# RX08b.net
KiCad netlist of a schematic drawn in EAGLE
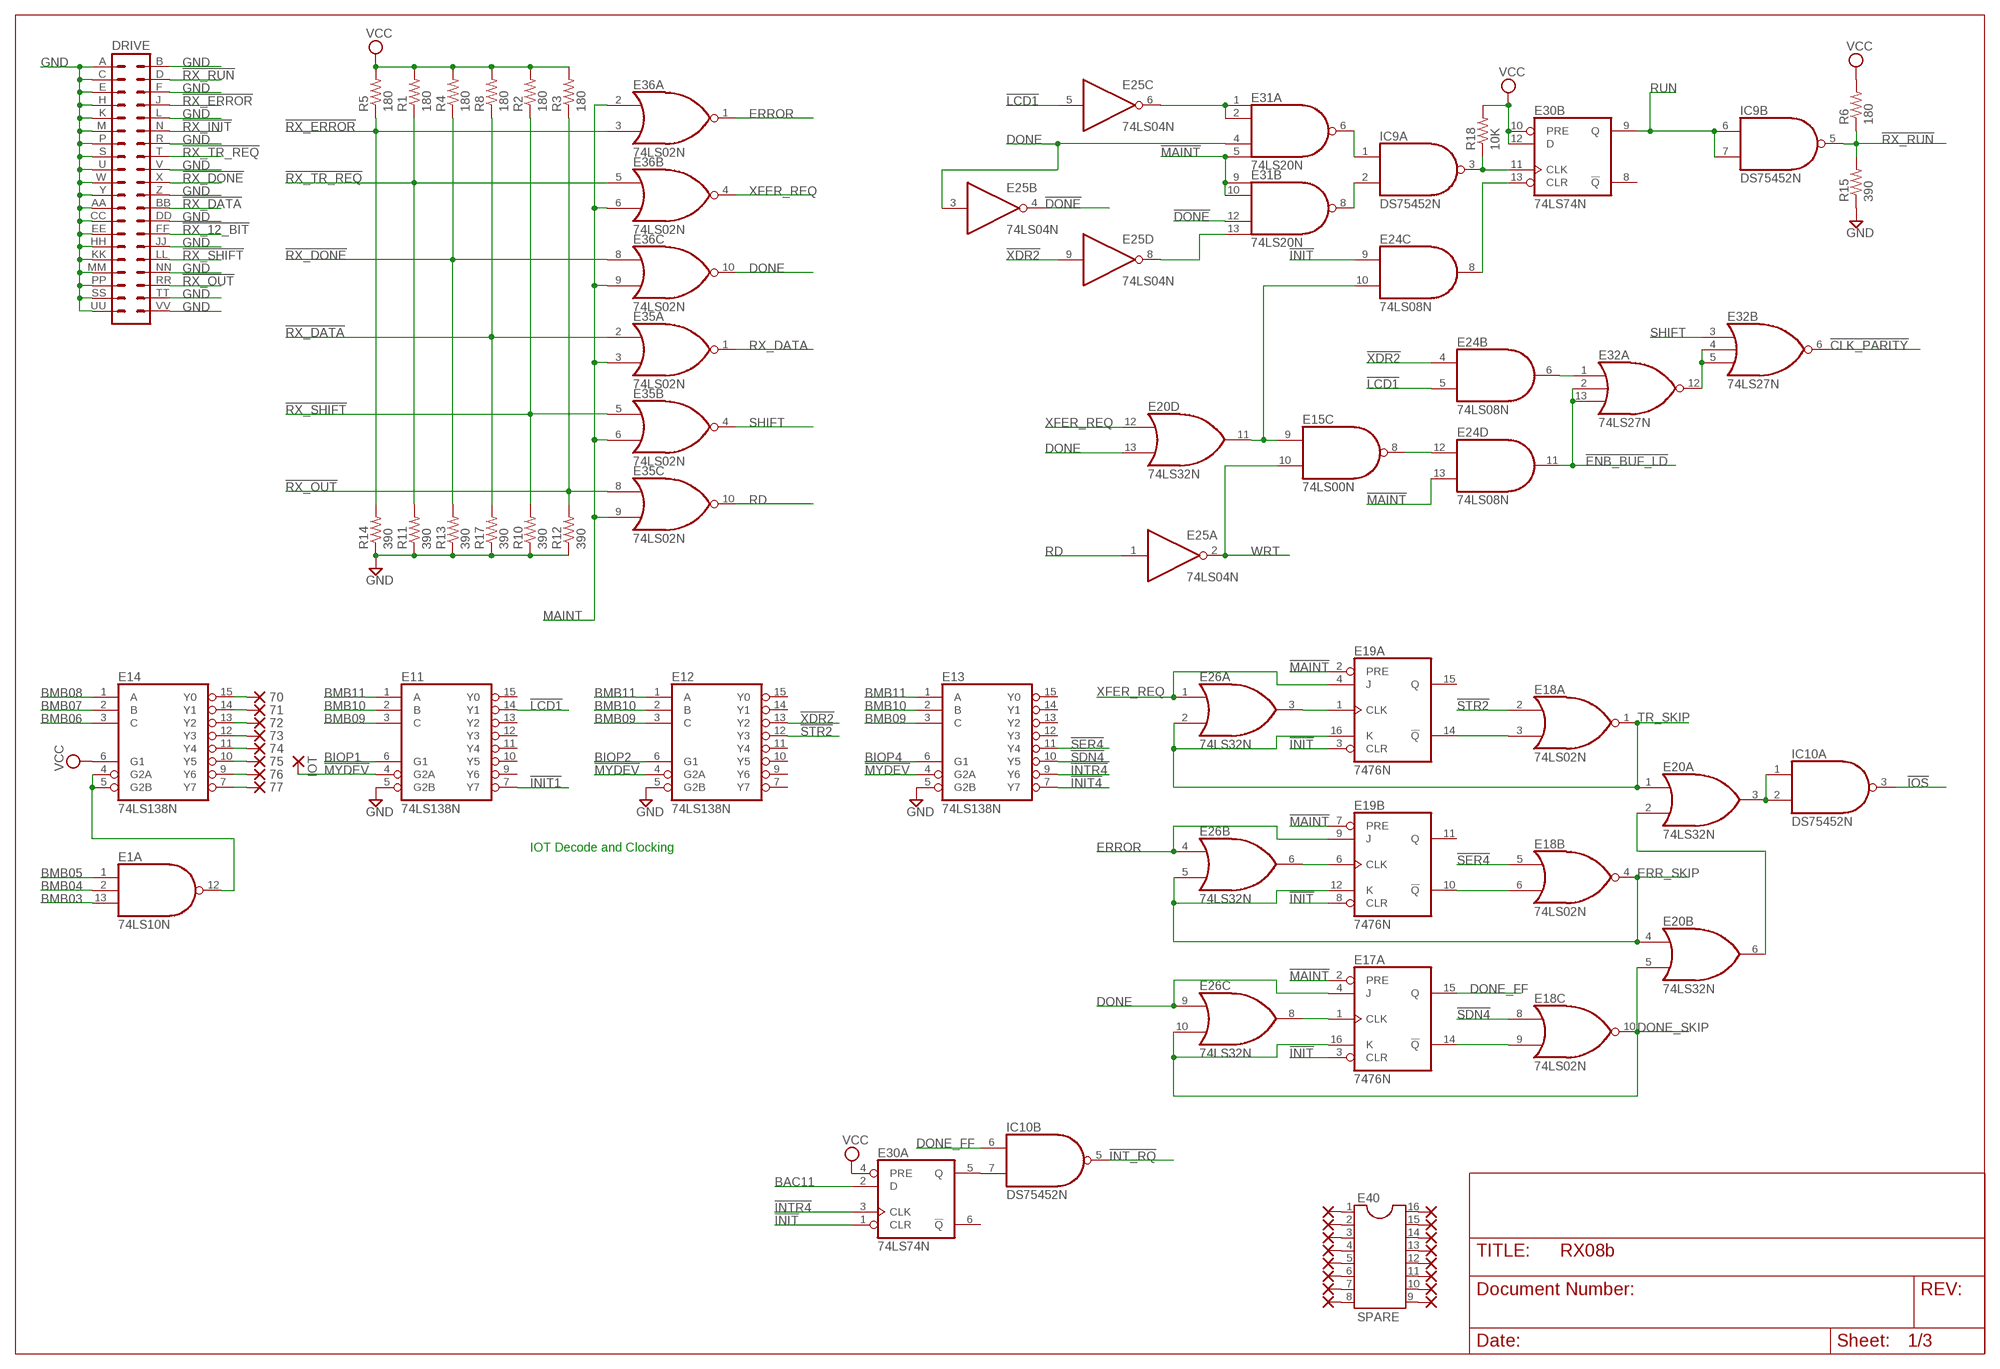
[diagram p0: schematic, sheet 1]
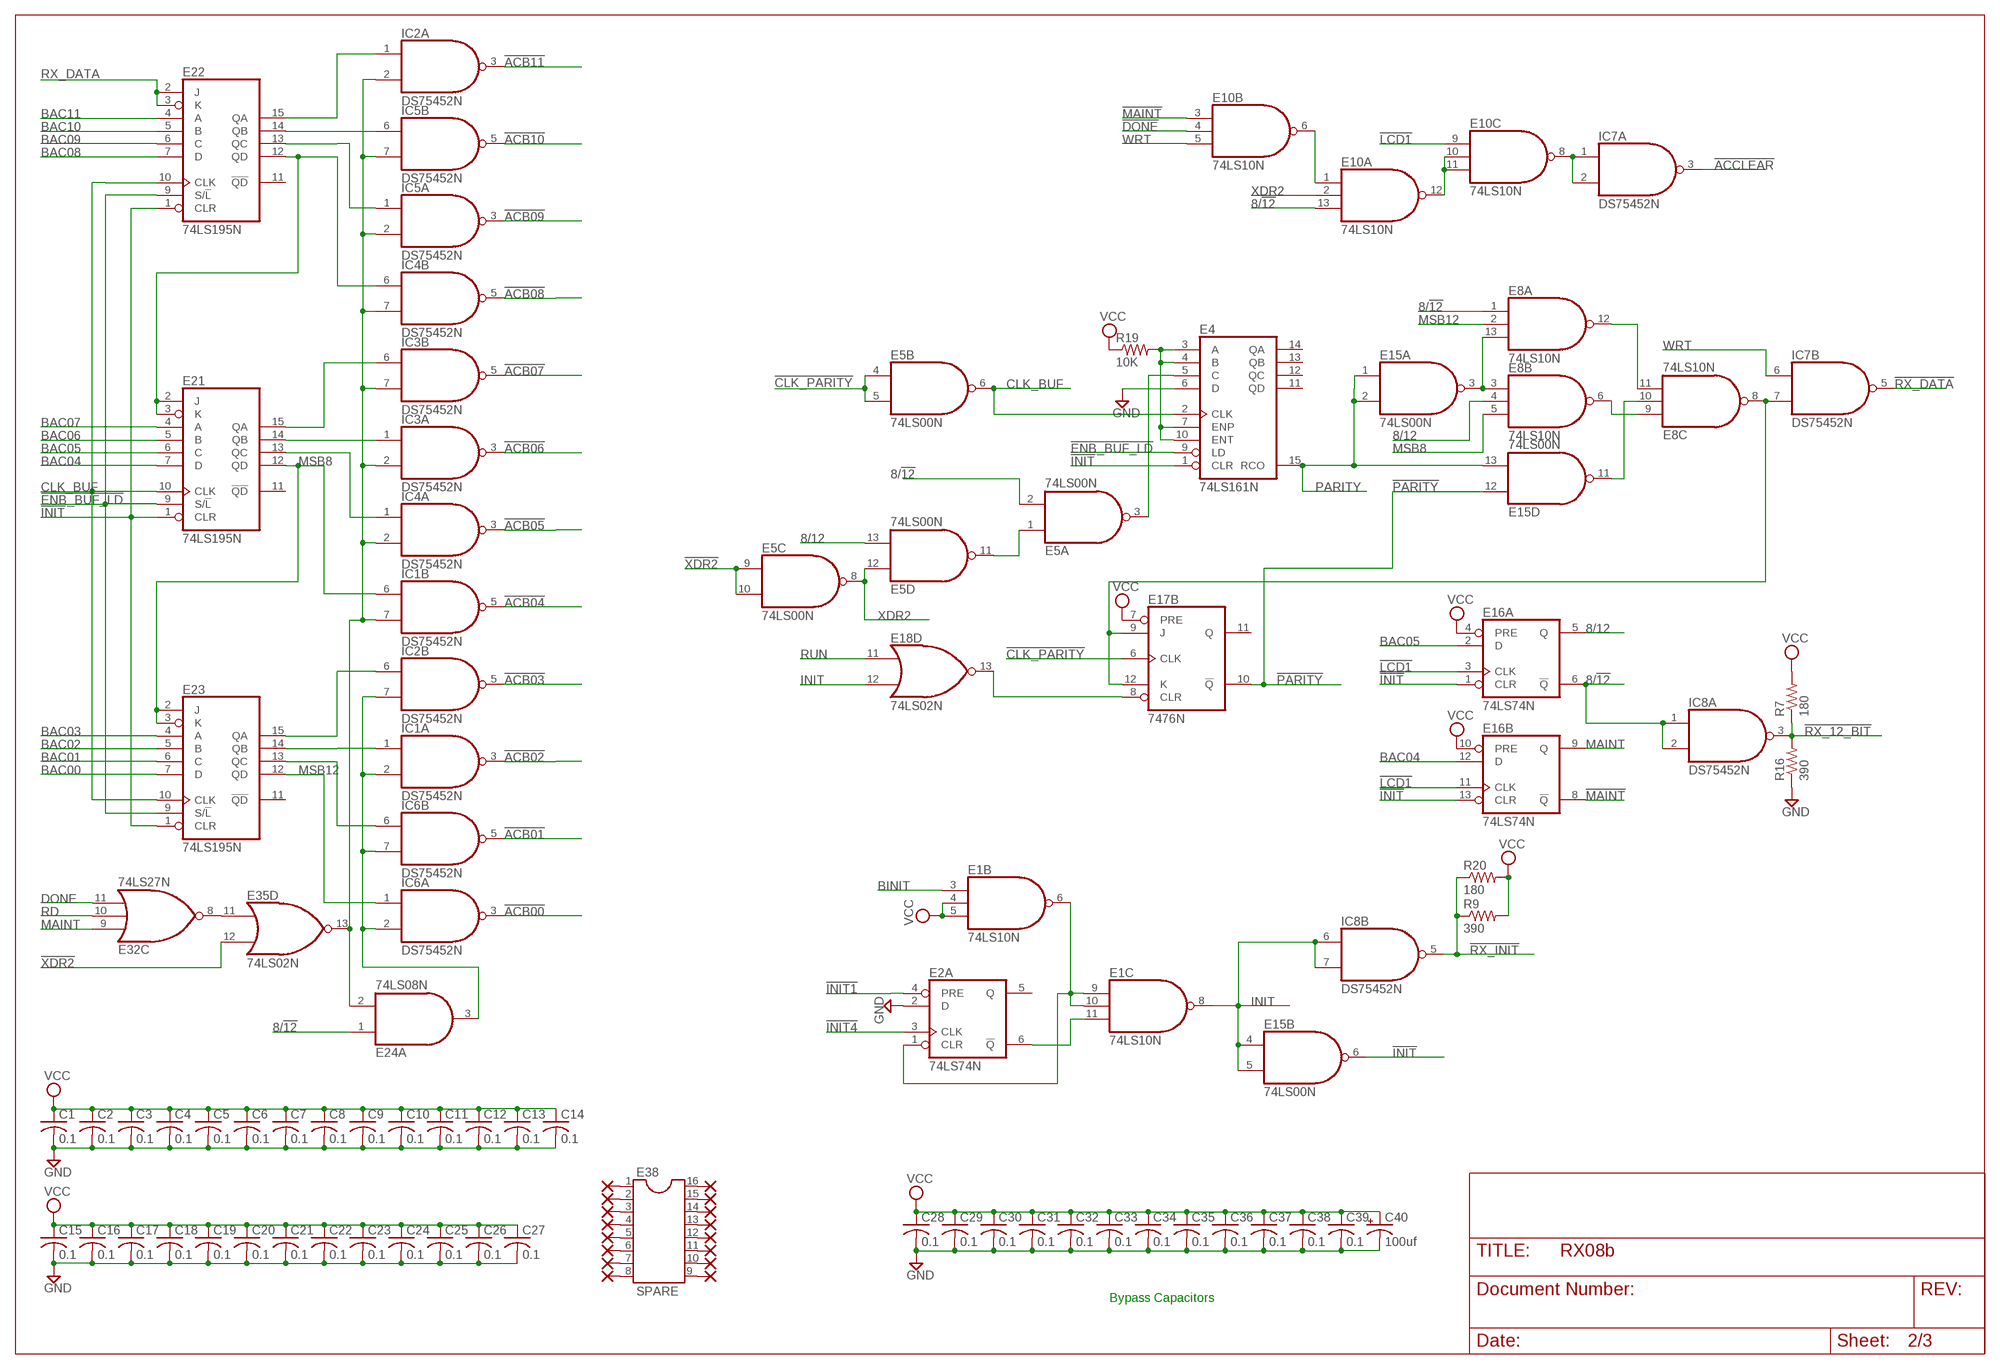
[diagram p1: schematic, sheet 2]
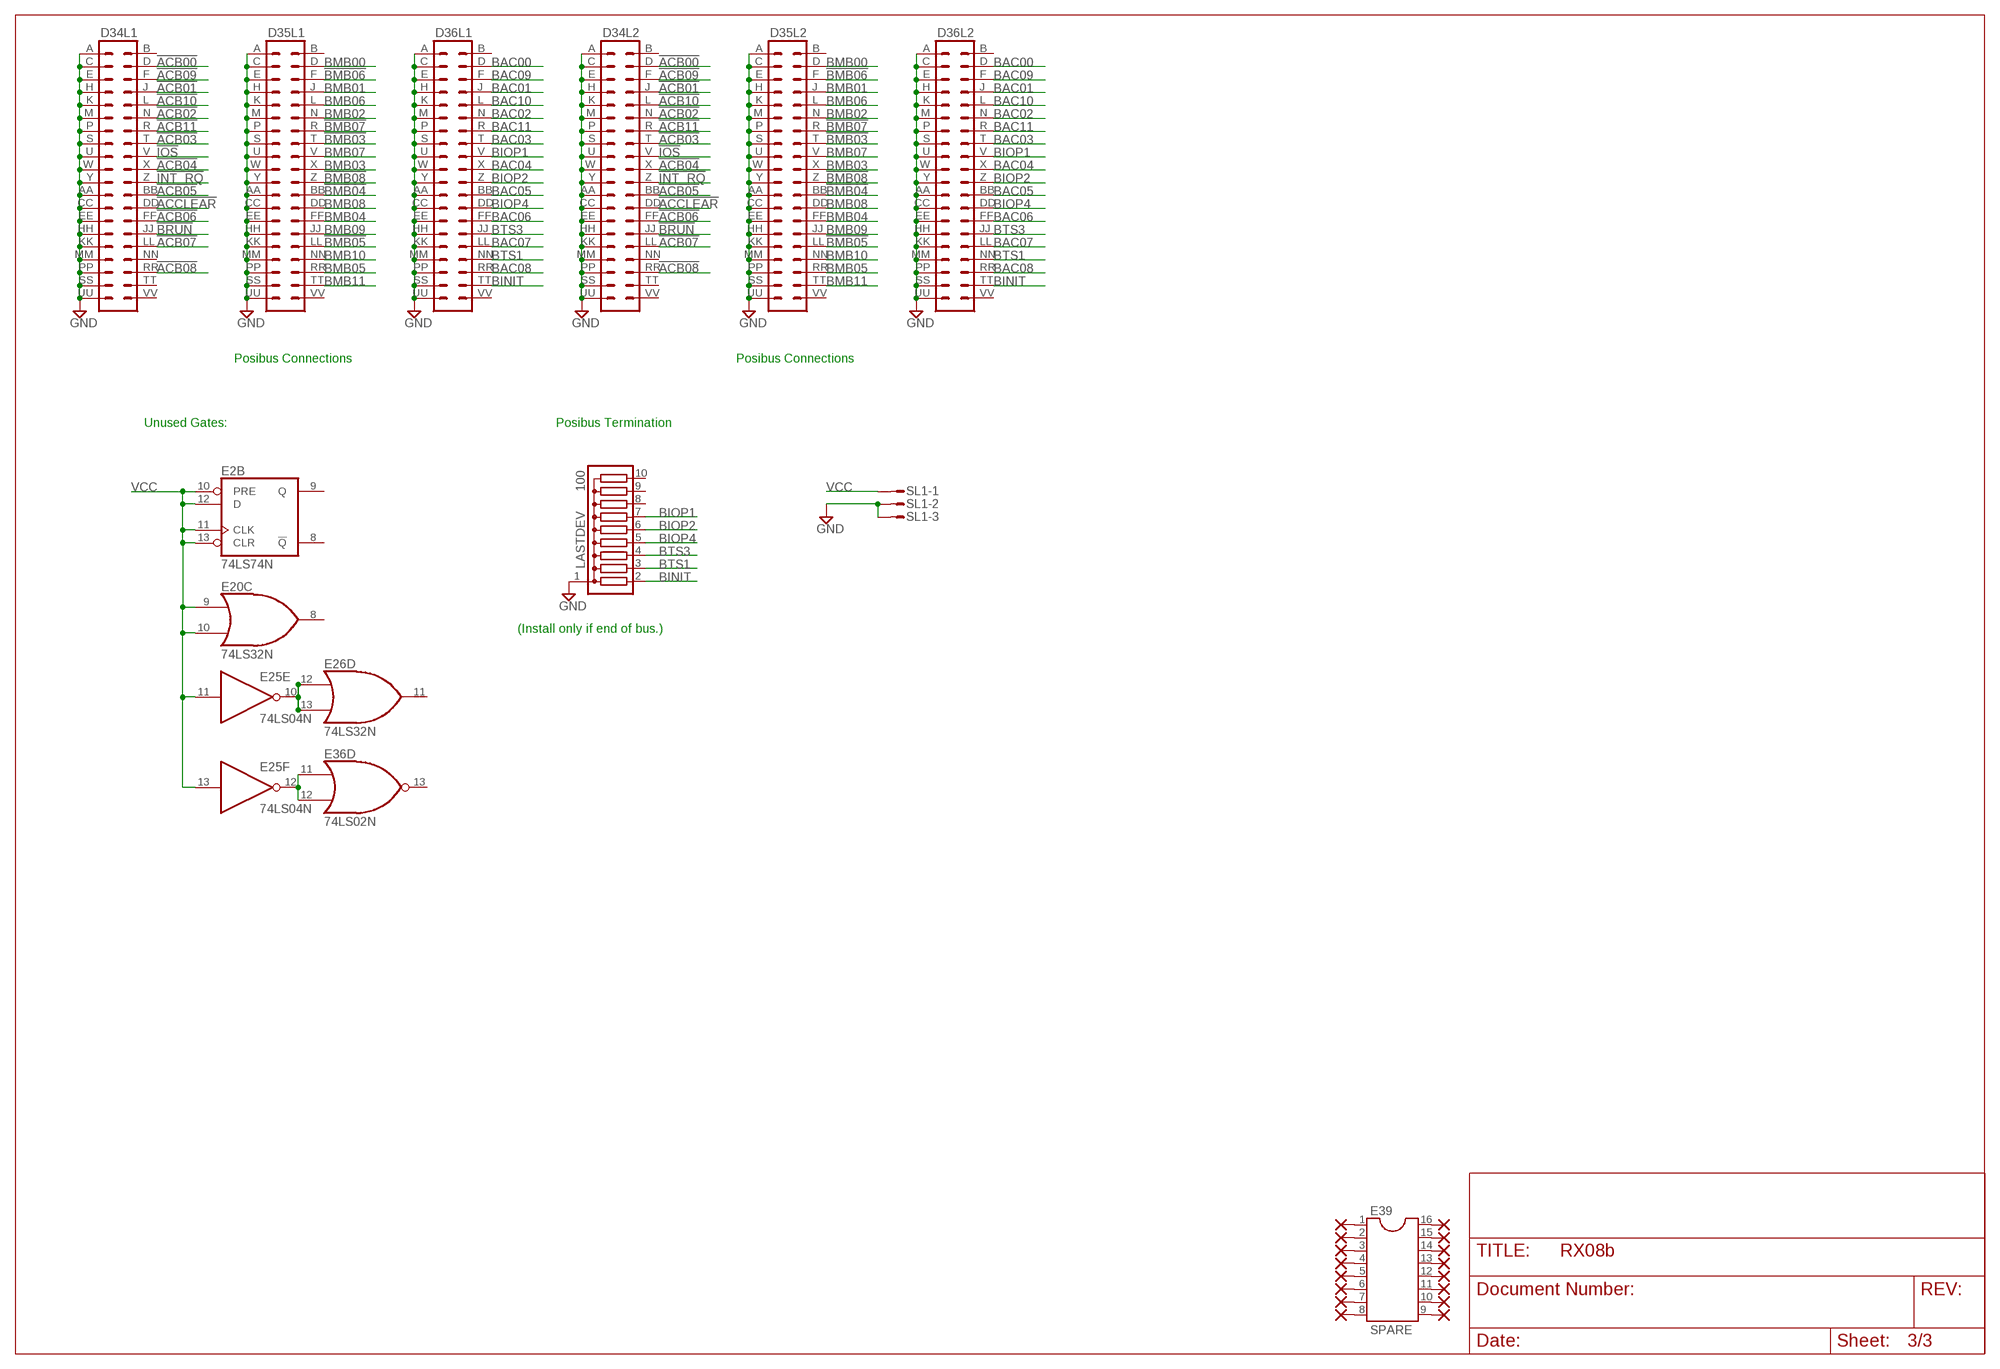
[diagram p2: schematic, sheet 3]

(export (version "E")
  (design (tool "Eeschema 10.0.6"))
  (components
    (comp (ref "C1")
      (value "0.1")
      (footprint "eagle-import:C050-025X075")
      (libsource (lib "eagle-import") (part "C-US050-025X075"))
    )
    (comp (ref "C2")
      (value "0.1")
      (footprint "eagle-import:C050-025X075")
      (libsource (lib "eagle-import") (part "C-US050-025X075"))
    )
    (comp (ref "C3")
      (value "0.1")
      (footprint "eagle-import:C050-025X075")
      (libsource (lib "eagle-import") (part "C-US050-025X075"))
    )
    (comp (ref "C4")
      (value "0.1")
      (footprint "eagle-import:C050-025X075")
      (libsource (lib "eagle-import") (part "C-US050-025X075"))
    )
    (comp (ref "C5")
      (value "0.1")
      (footprint "eagle-import:C050-025X075")
      (libsource (lib "eagle-import") (part "C-US050-025X075"))
    )
    (comp (ref "C6")
      (value "0.1")
      (footprint "eagle-import:C050-025X075")
      (libsource (lib "eagle-import") (part "C-US050-025X075"))
    )
    (comp (ref "C7")
      (value "0.1")
      (footprint "eagle-import:C050-025X075")
      (libsource (lib "eagle-import") (part "C-US050-025X075"))
    )
    (comp (ref "C8")
      (value "0.1")
      (footprint "eagle-import:C050-025X075")
      (libsource (lib "eagle-import") (part "C-US050-025X075"))
    )
    (comp (ref "C9")
      (value "0.1")
      (footprint "eagle-import:C050-025X075")
      (libsource (lib "eagle-import") (part "C-US050-025X075"))
    )
    (comp (ref "C10")
      (value "0.1")
      (footprint "eagle-import:C050-025X075")
      (libsource (lib "eagle-import") (part "C-US050-025X075"))
    )
    (comp (ref "C11")
      (value "0.1")
      (footprint "eagle-import:C050-025X075")
      (libsource (lib "eagle-import") (part "C-US050-025X075"))
    )
    (comp (ref "C12")
      (value "0.1")
      (footprint "eagle-import:C050-025X075")
      (libsource (lib "eagle-import") (part "C-US050-025X075"))
    )
    (comp (ref "C13")
      (value "0.1")
      (footprint "eagle-import:C050-025X075")
      (libsource (lib "eagle-import") (part "C-US050-025X075"))
    )
    (comp (ref "C14")
      (value "0.1")
      (footprint "eagle-import:C050-025X075")
      (libsource (lib "eagle-import") (part "C-US050-025X075"))
    )
    (comp (ref "C15")
      (value "0.1")
      (footprint "eagle-import:C050-025X075")
      (libsource (lib "eagle-import") (part "C-US050-025X075"))
    )
    (comp (ref "C16")
      (value "0.1")
      (footprint "eagle-import:C050-025X075")
      (libsource (lib "eagle-import") (part "C-US050-025X075"))
    )
    (comp (ref "C17")
      (value "0.1")
      (footprint "eagle-import:C050-025X075")
      (libsource (lib "eagle-import") (part "C-US050-025X075"))
    )
    (comp (ref "C18")
      (value "0.1")
      (footprint "eagle-import:C050-025X075")
      (libsource (lib "eagle-import") (part "C-US050-025X075"))
    )
    (comp (ref "C19")
      (value "0.1")
      (footprint "eagle-import:C050-025X075")
      (libsource (lib "eagle-import") (part "C-US050-025X075"))
    )
    (comp (ref "C20")
      (value "0.1")
      (footprint "eagle-import:C050-025X075")
      (libsource (lib "eagle-import") (part "C-US050-025X075"))
    )
    (comp (ref "C21")
      (value "0.1")
      (footprint "eagle-import:C050-025X075")
      (libsource (lib "eagle-import") (part "C-US050-025X075"))
    )
    (comp (ref "C22")
      (value "0.1")
      (footprint "eagle-import:C050-025X075")
      (libsource (lib "eagle-import") (part "C-US050-025X075"))
    )
    (comp (ref "C23")
      (value "0.1")
      (footprint "eagle-import:C050-025X075")
      (libsource (lib "eagle-import") (part "C-US050-025X075"))
    )
    (comp (ref "C24")
      (value "0.1")
      (footprint "eagle-import:C050-025X075")
      (libsource (lib "eagle-import") (part "C-US050-025X075"))
    )
    (comp (ref "C25")
      (value "0.1")
      (footprint "eagle-import:C050-025X075")
      (libsource (lib "eagle-import") (part "C-US050-025X075"))
    )
    (comp (ref "C26")
      (value "0.1")
      (footprint "eagle-import:C050-025X075")
      (libsource (lib "eagle-import") (part "C-US050-025X075"))
    )
    (comp (ref "C27")
      (value "0.1")
      (footprint "eagle-import:C050-025X075")
      (libsource (lib "eagle-import") (part "C-US050-025X075"))
    )
    (comp (ref "C28")
      (value "0.1")
      (footprint "eagle-import:C050-025X075")
      (libsource (lib "eagle-import") (part "C-US050-025X075"))
    )
    (comp (ref "C29")
      (value "0.1")
      (footprint "eagle-import:C050-025X075")
      (libsource (lib "eagle-import") (part "C-US050-025X075"))
    )
    (comp (ref "C30")
      (value "0.1")
      (footprint "eagle-import:C050-025X075")
      (libsource (lib "eagle-import") (part "C-US050-025X075"))
    )
    (comp (ref "C31")
      (value "0.1")
      (footprint "eagle-import:C050-025X075")
      (libsource (lib "eagle-import") (part "C-US050-025X075"))
    )
    (comp (ref "C32")
      (value "0.1")
      (footprint "eagle-import:C050-025X075")
      (libsource (lib "eagle-import") (part "C-US050-025X075"))
    )
    (comp (ref "C33")
      (value "0.1")
      (footprint "eagle-import:C050-025X075")
      (libsource (lib "eagle-import") (part "C-US050-025X075"))
    )
    (comp (ref "C34")
      (value "0.1")
      (footprint "eagle-import:C050-025X075")
      (libsource (lib "eagle-import") (part "C-US050-025X075"))
    )
    (comp (ref "C35")
      (value "0.1")
      (footprint "eagle-import:C050-025X075")
      (libsource (lib "eagle-import") (part "C-US050-025X075"))
    )
    (comp (ref "C36")
      (value "0.1")
      (footprint "eagle-import:C050-025X075")
      (libsource (lib "eagle-import") (part "C-US050-025X075"))
    )
    (comp (ref "C37")
      (value "0.1")
      (footprint "eagle-import:C050-025X075")
      (libsource (lib "eagle-import") (part "C-US050-025X075"))
    )
    (comp (ref "C38")
      (value "0.1")
      (footprint "eagle-import:C050-025X075")
      (libsource (lib "eagle-import") (part "C-US050-025X075"))
    )
    (comp (ref "C39")
      (value "0.1")
      (footprint "eagle-import:C050-025X075")
      (libsource (lib "eagle-import") (part "C-US050-025X075"))
    )
    (comp (ref "C40")
      (value "100uf")
      (footprint "eagle-import:E22-9")
      (libsource (lib "eagle-import") (part "CPOL-USE22-9AXIAL"))
    )
    (comp (ref "E1")
      (value "74LS10N")
      (footprint "eagle-import:DIL14")
      (libsource (lib "eagle-import") (part "7410NLS"))
    )
    (comp (ref "E2")
      (value "74LS74N")
      (footprint "eagle-import:DIL14")
      (libsource (lib "eagle-import") (part "7474NLS"))
    )
    (comp (ref "E4")
      (value "74LS161N")
      (footprint "eagle-import:DIL16")
      (libsource (lib "eagle-import") (part "74161NLS"))
    )
    (comp (ref "E5")
      (value "74LS00N")
      (footprint "eagle-import:DIL14")
      (libsource (lib "eagle-import") (part "7400NLS"))
    )
    (comp (ref "E8")
      (value "74LS10N")
      (footprint "eagle-import:DIL14")
      (libsource (lib "eagle-import") (part "7410NLS"))
    )
    (comp (ref "E10")
      (value "74LS10N")
      (footprint "eagle-import:DIL14")
      (libsource (lib "eagle-import") (part "7410NLS"))
    )
    (comp (ref "E15")
      (value "74LS00N")
      (footprint "eagle-import:DIL14")
      (libsource (lib "eagle-import") (part "7400NLS"))
    )
    (comp (ref "E16")
      (value "74LS74N")
      (footprint "eagle-import:DIL14")
      (libsource (lib "eagle-import") (part "7474NLS"))
    )
    (comp (ref "E17")
      (value "7476N")
      (footprint "eagle-import:DIL16")
      (libsource (lib "eagle-import") (part "7476N"))
    )
    (comp (ref "E18")
      (value "74LS02N")
      (footprint "eagle-import:DIL14")
      (libsource (lib "eagle-import") (part "7402NLS"))
    )
    (comp (ref "E21")
      (value "74LS195N")
      (footprint "eagle-import:DIL16")
      (libsource (lib "eagle-import") (part "74195NLS"))
    )
    (comp (ref "E22")
      (value "74LS195N")
      (footprint "eagle-import:DIL16")
      (libsource (lib "eagle-import") (part "74195NLS"))
    )
    (comp (ref "E23")
      (value "74LS195N")
      (footprint "eagle-import:DIL16")
      (libsource (lib "eagle-import") (part "74195NLS"))
    )
    (comp (ref "E24")
      (value "74LS08N")
      (footprint "eagle-import:DIL14")
      (libsource (lib "eagle-import") (part "7408NLS"))
    )
    (comp (ref "E32")
      (value "74LS27N")
      (footprint "eagle-import:DIL14")
      (libsource (lib "eagle-import") (part "7427NLS"))
    )
    (comp (ref "E35")
      (value "74LS02N")
      (footprint "eagle-import:DIL14")
      (libsource (lib "eagle-import") (part "7402NLS"))
    )
    (comp (ref "E38")
      (value "SPARE")
      (footprint "eagle-import:DIL16")
      (libsource (lib "eagle-import") (part "DIL16"))
    )
    (comp (ref "IC1")
      (value "DS75452N")
      (footprint "eagle-import:DIL08")
      (libsource (lib "eagle-import") (part "DS75452N"))
    )
    (comp (ref "IC2")
      (value "DS75452N")
      (footprint "eagle-import:DIL08")
      (libsource (lib "eagle-import") (part "DS75452N"))
    )
    (comp (ref "IC3")
      (value "DS75452N")
      (footprint "eagle-import:DIL08")
      (libsource (lib "eagle-import") (part "DS75452N"))
    )
    (comp (ref "IC4")
      (value "DS75452N")
      (footprint "eagle-import:DIL08")
      (libsource (lib "eagle-import") (part "DS75452N"))
    )
    (comp (ref "IC5")
      (value "DS75452N")
      (footprint "eagle-import:DIL08")
      (libsource (lib "eagle-import") (part "DS75452N"))
    )
    (comp (ref "IC6")
      (value "DS75452N")
      (footprint "eagle-import:DIL08")
      (libsource (lib "eagle-import") (part "DS75452N"))
    )
    (comp (ref "IC7")
      (value "DS75452N")
      (footprint "eagle-import:DIL08")
      (libsource (lib "eagle-import") (part "DS75452N"))
    )
    (comp (ref "IC8")
      (value "DS75452N")
      (footprint "eagle-import:DIL08")
      (libsource (lib "eagle-import") (part "DS75452N"))
    )
    (comp (ref "PAD10")
      (value "1,6/0,8")
      (footprint "eagle-import:1,6_0,8")
      (libsource (lib "eagle-import") (part "1,6/0,8"))
    )
    (comp (ref "PAD11")
      (value "1,6/0,8")
      (footprint "eagle-import:1,6_0,8")
      (libsource (lib "eagle-import") (part "1,6/0,8"))
    )
    (comp (ref "PAD12")
      (value "1,6/0,8")
      (footprint "eagle-import:1,6_0,8")
      (libsource (lib "eagle-import") (part "1,6/0,8"))
    )
    (comp (ref "PAD13")
      (value "1,6/0,8")
      (footprint "eagle-import:1,6_0,8")
      (libsource (lib "eagle-import") (part "1,6/0,8"))
    )
    (comp (ref "PAD14")
      (value "1,6/0,8")
      (footprint "eagle-import:1,6_0,8")
      (libsource (lib "eagle-import") (part "1,6/0,8"))
    )
    (comp (ref "PAD15")
      (value "1,6/0,8")
      (footprint "eagle-import:1,6_0,8")
      (libsource (lib "eagle-import") (part "1,6/0,8"))
    )
    (comp (ref "PAD16")
      (value "1,6/0,8")
      (footprint "eagle-import:1,6_0,8")
      (libsource (lib "eagle-import") (part "1,6/0,8"))
    )
    (comp (ref "PAD17")
      (value "1,6/0,8")
      (footprint "eagle-import:1,6_0,8")
      (libsource (lib "eagle-import") (part "1,6/0,8"))
    )
    (comp (ref "PAD20")
      (value "1,6/0,8")
      (footprint "eagle-import:1,6_0,8")
      (libsource (lib "eagle-import") (part "1,6/0,8"))
    )
    (comp (ref "PAD21")
      (value "1,6/0,8")
      (footprint "eagle-import:1,6_0,8")
      (libsource (lib "eagle-import") (part "1,6/0,8"))
    )
    (comp (ref "PAD22")
      (value "1,6/0,8")
      (footprint "eagle-import:1,6_0,8")
      (libsource (lib "eagle-import") (part "1,6/0,8"))
    )
    (comp (ref "PAD23")
      (value "1,6/0,8")
      (footprint "eagle-import:1,6_0,8")
      (libsource (lib "eagle-import") (part "1,6/0,8"))
    )
    (comp (ref "PAD24")
      (value "1,6/0,8")
      (footprint "eagle-import:1,6_0,8")
      (libsource (lib "eagle-import") (part "1,6/0,8"))
    )
    (comp (ref "PAD25")
      (value "1,6/0,8")
      (footprint "eagle-import:1,6_0,8")
      (libsource (lib "eagle-import") (part "1,6/0,8"))
    )
    (comp (ref "PAD26")
      (value "1,6/0,8")
      (footprint "eagle-import:1,6_0,8")
      (libsource (lib "eagle-import") (part "1,6/0,8"))
    )
    (comp (ref "PAD27")
      (value "1,6/0,8")
      (footprint "eagle-import:1,6_0,8")
      (libsource (lib "eagle-import") (part "1,6/0,8"))
    )
    (comp (ref "R7")
      (value "180")
      (footprint "eagle-import:0207_10")
      (libsource (lib "eagle-import") (part "R-US_0207/10"))
    )
    (comp (ref "R9")
      (value "390")
      (footprint "eagle-import:0207_10")
      (libsource (lib "eagle-import") (part "R-US_0207/10"))
    )
    (comp (ref "R16")
      (value "390")
      (footprint "eagle-import:0207_10")
      (libsource (lib "eagle-import") (part "R-US_0207/10"))
    )
    (comp (ref "R19")
      (value "10K")
      (footprint "eagle-import:0207_10")
      (libsource (lib "eagle-import") (part "R-US_0207/10"))
    )
    (comp (ref "R20")
      (value "180")
      (footprint "eagle-import:0207_10")
      (libsource (lib "eagle-import") (part "R-US_0207/10"))
    )
    (comp (ref "70")
      (value "1,6/0,8")
      (footprint "eagle-import:1,6_0,8")
      (libsource (lib "eagle-import") (part "1,6/0,8"))
    )
    (comp (ref "71")
      (value "1,6/0,8")
      (footprint "eagle-import:1,6_0,8")
      (libsource (lib "eagle-import") (part "1,6/0,8"))
    )
    (comp (ref "72")
      (value "1,6/0,8")
      (footprint "eagle-import:1,6_0,8")
      (libsource (lib "eagle-import") (part "1,6/0,8"))
    )
    (comp (ref "73")
      (value "1,6/0,8")
      (footprint "eagle-import:1,6_0,8")
      (libsource (lib "eagle-import") (part "1,6/0,8"))
    )
    (comp (ref "74")
      (value "1,6/0,8")
      (footprint "eagle-import:1,6_0,8")
      (libsource (lib "eagle-import") (part "1,6/0,8"))
    )
    (comp (ref "75")
      (value "1,6/0,8")
      (footprint "eagle-import:1,6_0,8")
      (libsource (lib "eagle-import") (part "1,6/0,8"))
    )
    (comp (ref "76")
      (value "1,6/0,8")
      (footprint "eagle-import:1,6_0,8")
      (libsource (lib "eagle-import") (part "1,6/0,8"))
    )
    (comp (ref "77")
      (value "1,6/0,8")
      (footprint "eagle-import:1,6_0,8")
      (libsource (lib "eagle-import") (part "1,6/0,8"))
    )
    (comp (ref "DRIVE")
      (value "DEC40PINV")
      (footprint "eagle-import:DEC40PINV")
      (libsource (lib "eagle-import") (part "DEC40PINV"))
    )
    (comp (ref "E11")
      (value "74LS138N")
      (footprint "eagle-import:DIL16")
      (libsource (lib "eagle-import") (part "74138NLS"))
    )
    (comp (ref "E12")
      (value "74LS138N")
      (footprint "eagle-import:DIL16")
      (libsource (lib "eagle-import") (part "74138NLS"))
    )
    (comp (ref "E13")
      (value "74LS138N")
      (footprint "eagle-import:DIL16")
      (libsource (lib "eagle-import") (part "74138NLS"))
    )
    (comp (ref "E14")
      (value "74LS138N")
      (footprint "eagle-import:DIL16")
      (libsource (lib "eagle-import") (part "74138NLS"))
    )
    (comp (ref "E19")
      (value "7476N")
      (footprint "eagle-import:DIL16")
      (libsource (lib "eagle-import") (part "7476N"))
    )
    (comp (ref "E20")
      (value "74LS32N")
      (footprint "eagle-import:DIL14")
      (libsource (lib "eagle-import") (part "7432NLS"))
    )
    (comp (ref "E25")
      (value "74LS04N")
      (footprint "eagle-import:DIL14")
      (libsource (lib "eagle-import") (part "7404NLS"))
    )
    (comp (ref "E26")
      (value "74LS32N")
      (footprint "eagle-import:DIL14")
      (libsource (lib "eagle-import") (part "7432NLS"))
    )
    (comp (ref "E30")
      (value "74LS74N")
      (footprint "eagle-import:DIL14")
      (libsource (lib "eagle-import") (part "7474NLS"))
    )
    (comp (ref "E31")
      (value "74LS20N")
      (footprint "eagle-import:DIL14")
      (libsource (lib "eagle-import") (part "7420NLS"))
    )
    (comp (ref "E36")
      (value "74LS02N")
      (footprint "eagle-import:DIL14")
      (libsource (lib "eagle-import") (part "7402NLS"))
    )
    (comp (ref "E40")
      (value "SPARE")
      (footprint "eagle-import:DIL16")
      (libsource (lib "eagle-import") (part "DIL16"))
    )
    (comp (ref "IC9")
      (value "DS75452N")
      (footprint "eagle-import:DIL08")
      (libsource (lib "eagle-import") (part "DS75452N"))
    )
    (comp (ref "IC10")
      (value "DS75452N")
      (footprint "eagle-import:DIL08")
      (libsource (lib "eagle-import") (part "DS75452N"))
    )
    (comp (ref "IOT")
      (value "1,6/0,8")
      (footprint "eagle-import:1,6_0,8")
      (libsource (lib "eagle-import") (part "1,6/0,8"))
    )
    (comp (ref "PAD18")
      (value "1,6/0,8")
      (footprint "eagle-import:1,6_0,8")
      (libsource (lib "eagle-import") (part "1,6/0,8"))
    )
    (comp (ref "PAD19")
      (value "1,6/0,8")
      (footprint "eagle-import:1,6_0,8")
      (libsource (lib "eagle-import") (part "1,6/0,8"))
    )
    (comp (ref "PAD28")
      (value "1,6/0,8")
      (footprint "eagle-import:1,6_0,8")
      (libsource (lib "eagle-import") (part "1,6/0,8"))
    )
    (comp (ref "PAD29")
      (value "1,6/0,8")
      (footprint "eagle-import:1,6_0,8")
      (libsource (lib "eagle-import") (part "1,6/0,8"))
    )
    (comp (ref "PAD30")
      (value "1,6/0,8")
      (footprint "eagle-import:1,6_0,8")
      (libsource (lib "eagle-import") (part "1,6/0,8"))
    )
    (comp (ref "PAD31")
      (value "1,6/0,8")
      (footprint "eagle-import:1,6_0,8")
      (libsource (lib "eagle-import") (part "1,6/0,8"))
    )
    (comp (ref "PAD32")
      (value "1,6/0,8")
      (footprint "eagle-import:1,6_0,8")
      (libsource (lib "eagle-import") (part "1,6/0,8"))
    )
    (comp (ref "PAD33")
      (value "1,6/0,8")
      (footprint "eagle-import:1,6_0,8")
      (libsource (lib "eagle-import") (part "1,6/0,8"))
    )
    (comp (ref "PAD34")
      (value "1,6/0,8")
      (footprint "eagle-import:1,6_0,8")
      (libsource (lib "eagle-import") (part "1,6/0,8"))
    )
    (comp (ref "PAD35")
      (value "1,6/0,8")
      (footprint "eagle-import:1,6_0,8")
      (libsource (lib "eagle-import") (part "1,6/0,8"))
    )
    (comp (ref "PAD36")
      (value "1,6/0,8")
      (footprint "eagle-import:1,6_0,8")
      (libsource (lib "eagle-import") (part "1,6/0,8"))
    )
    (comp (ref "PAD37")
      (value "1,6/0,8")
      (footprint "eagle-import:1,6_0,8")
      (libsource (lib "eagle-import") (part "1,6/0,8"))
    )
    (comp (ref "PAD38")
      (value "1,6/0,8")
      (footprint "eagle-import:1,6_0,8")
      (libsource (lib "eagle-import") (part "1,6/0,8"))
    )
    (comp (ref "PAD39")
      (value "1,6/0,8")
      (footprint "eagle-import:1,6_0,8")
      (libsource (lib "eagle-import") (part "1,6/0,8"))
    )
    (comp (ref "PAD40")
      (value "1,6/0,8")
      (footprint "eagle-import:1,6_0,8")
      (libsource (lib "eagle-import") (part "1,6/0,8"))
    )
    (comp (ref "PAD41")
      (value "1,6/0,8")
      (footprint "eagle-import:1,6_0,8")
      (libsource (lib "eagle-import") (part "1,6/0,8"))
    )
    (comp (ref "R1")
      (value "180")
      (footprint "eagle-import:0207_10")
      (libsource (lib "eagle-import") (part "R-US_0207/10"))
    )
    (comp (ref "R2")
      (value "180")
      (footprint "eagle-import:0207_10")
      (libsource (lib "eagle-import") (part "R-US_0207/10"))
    )
    (comp (ref "R3")
      (value "180")
      (footprint "eagle-import:0207_10")
      (libsource (lib "eagle-import") (part "R-US_0207/10"))
    )
    (comp (ref "R4")
      (value "180")
      (footprint "eagle-import:0207_10")
      (libsource (lib "eagle-import") (part "R-US_0207/10"))
    )
    (comp (ref "R5")
      (value "180")
      (footprint "eagle-import:0207_10")
      (libsource (lib "eagle-import") (part "R-US_0207/10"))
    )
    (comp (ref "R6")
      (value "180")
      (footprint "eagle-import:0207_10")
      (libsource (lib "eagle-import") (part "R-US_0207/10"))
    )
    (comp (ref "R8")
      (value "180")
      (footprint "eagle-import:0207_10")
      (libsource (lib "eagle-import") (part "R-US_0207/10"))
    )
    (comp (ref "R10")
      (value "390")
      (footprint "eagle-import:0207_10")
      (libsource (lib "eagle-import") (part "R-US_0207/10"))
    )
    (comp (ref "R11")
      (value "390")
      (footprint "eagle-import:0207_10")
      (libsource (lib "eagle-import") (part "R-US_0207/10"))
    )
    (comp (ref "R12")
      (value "390")
      (footprint "eagle-import:0207_10")
      (libsource (lib "eagle-import") (part "R-US_0207/10"))
    )
    (comp (ref "R13")
      (value "390")
      (footprint "eagle-import:0207_10")
      (libsource (lib "eagle-import") (part "R-US_0207/10"))
    )
    (comp (ref "R14")
      (value "390")
      (footprint "eagle-import:0207_10")
      (libsource (lib "eagle-import") (part "R-US_0207/10"))
    )
    (comp (ref "R15")
      (value "390")
      (footprint "eagle-import:0207_10")
      (libsource (lib "eagle-import") (part "R-US_0207/10"))
    )
    (comp (ref "R17")
      (value "390")
      (footprint "eagle-import:0207_10")
      (libsource (lib "eagle-import") (part "R-US_0207/10"))
    )
    (comp (ref "R18")
      (value "10K")
      (footprint "eagle-import:0207_10")
      (libsource (lib "eagle-import") (part "R-US_0207/10"))
    )
    (comp (ref "D34L1")
      (value "DEC40PINV")
      (footprint "eagle-import:DEC40PINV")
      (libsource (lib "eagle-import") (part "DEC40PINV"))
    )
    (comp (ref "D34L2")
      (value "DEC40PINV")
      (footprint "eagle-import:DEC40PINV")
      (libsource (lib "eagle-import") (part "DEC40PINV"))
    )
    (comp (ref "D35L1")
      (value "DEC40PINV")
      (footprint "eagle-import:DEC40PINV")
      (libsource (lib "eagle-import") (part "DEC40PINV"))
    )
    (comp (ref "D35L2")
      (value "DEC40PINV")
      (footprint "eagle-import:DEC40PINV")
      (libsource (lib "eagle-import") (part "DEC40PINV"))
    )
    (comp (ref "D36L1")
      (value "DEC40PINV")
      (footprint "eagle-import:DEC40PINV")
      (libsource (lib "eagle-import") (part "DEC40PINV"))
    )
    (comp (ref "D36L2")
      (value "DEC40PINV")
      (footprint "eagle-import:DEC40PINV")
      (libsource (lib "eagle-import") (part "DEC40PINV"))
    )
    (comp (ref "E39")
      (value "SPARE")
      (footprint "eagle-import:DIL16")
      (libsource (lib "eagle-import") (part "DIL16"))
    )
    (comp (ref "LASTDEV")
      (value "100")
      (footprint "eagle-import:SIL10")
      (libsource (lib "eagle-import") (part "G09R"))
    )
    (comp (ref "PAD42")
      (value "1,6/0,8")
      (footprint "eagle-import:1,6_0,8")
      (libsource (lib "eagle-import") (part "1,6/0,8"))
    )
    (comp (ref "PAD43")
      (value "1,6/0,8")
      (footprint "eagle-import:1,6_0,8")
      (libsource (lib "eagle-import") (part "1,6/0,8"))
    )
    (comp (ref "PAD44")
      (value "1,6/0,8")
      (footprint "eagle-import:1,6_0,8")
      (libsource (lib "eagle-import") (part "1,6/0,8"))
    )
    (comp (ref "PAD45")
      (value "1,6/0,8")
      (footprint "eagle-import:1,6_0,8")
      (libsource (lib "eagle-import") (part "1,6/0,8"))
    )
    (comp (ref "PAD46")
      (value "1,6/0,8")
      (footprint "eagle-import:1,6_0,8")
      (libsource (lib "eagle-import") (part "1,6/0,8"))
    )
    (comp (ref "PAD47")
      (value "1,6/0,8")
      (footprint "eagle-import:1,6_0,8")
      (libsource (lib "eagle-import") (part "1,6/0,8"))
    )
    (comp (ref "PAD48")
      (value "1,6/0,8")
      (footprint "eagle-import:1,6_0,8")
      (libsource (lib "eagle-import") (part "1,6/0,8"))
    )
    (comp (ref "PAD49")
      (value "1,6/0,8")
      (footprint "eagle-import:1,6_0,8")
      (libsource (lib "eagle-import") (part "1,6/0,8"))
    )
    (comp (ref "PAD50")
      (value "1,6/0,8")
      (footprint "eagle-import:1,6_0,8")
      (libsource (lib "eagle-import") (part "1,6/0,8"))
    )
    (comp (ref "PAD51")
      (value "1,6/0,8")
      (footprint "eagle-import:1,6_0,8")
      (libsource (lib "eagle-import") (part "1,6/0,8"))
    )
    (comp (ref "PAD52")
      (value "1,6/0,8")
      (footprint "eagle-import:1,6_0,8")
      (libsource (lib "eagle-import") (part "1,6/0,8"))
    )
    (comp (ref "PAD53")
      (value "1,6/0,8")
      (footprint "eagle-import:1,6_0,8")
      (libsource (lib "eagle-import") (part "1,6/0,8"))
    )
    (comp (ref "PAD54")
      (value "1,6/0,8")
      (footprint "eagle-import:1,6_0,8")
      (libsource (lib "eagle-import") (part "1,6/0,8"))
    )
    (comp (ref "PAD55")
      (value "1,6/0,8")
      (footprint "eagle-import:1,6_0,8")
      (libsource (lib "eagle-import") (part "1,6/0,8"))
    )
    (comp (ref "PAD56")
      (value "1,6/0,8")
      (footprint "eagle-import:1,6_0,8")
      (libsource (lib "eagle-import") (part "1,6/0,8"))
    )
    (comp (ref "PAD57")
      (value "1,6/0,8")
      (footprint "eagle-import:1,6_0,8")
      (libsource (lib "eagle-import") (part "1,6/0,8"))
    )
    (comp (ref "SL1")
      (value "MA04S")
      (footprint "eagle-import:04PA")
      (libsource (lib "eagle-import") (part "MA04S"))
    )
  )
  (nets
    (net (code "1") (name "8{slash}12") (class "Default")
      (node (ref "E16") (pin "5") (pinfunction "Q_5") (pintype "output"))
      (node (ref "E5") (pin "13") (pinfunction "I1_13") (pintype "input"))
      (node (ref "E8") (pin "4") (pinfunction "I1_4") (pintype "input"))
    )
    (net (code "2") (name "8{slash}~{12}") (class "Default")
      (node (ref "E10") (pin "13") (pinfunction "I2_13") (pintype "input"))
      (node (ref "E16") (pin "6") (pinfunction "~{Q}_6") (pintype "output"))
      (node (ref "E24") (pin "1") (pinfunction "I0_1") (pintype "input"))
      (node (ref "E5") (pin "2") (pinfunction "I1_2") (pintype "input"))
      (node (ref "E8") (pin "1") (pinfunction "I0_1") (pintype "input"))
      (node (ref "IC8") (pin "1") (pinfunction "I0_1") (pintype "input"))
      (node (ref "IC8") (pin "2") (pinfunction "I1_2") (pintype "input"))
    )
    (net (code "3") (name "BAC00") (class "Default")
      (node (ref "D36L1") (pin "D") (pinfunction "4_D") (pintype "bidirectional"))
      (node (ref "D36L2") (pin "D") (pinfunction "4_D") (pintype "bidirectional"))
      (node (ref "E23") (pin "7") (pinfunction "D_7") (pintype "input"))
    )
    (net (code "4") (name "BAC01") (class "Default")
      (node (ref "D36L1") (pin "J") (pinfunction "8_J") (pintype "bidirectional"))
      (node (ref "D36L2") (pin "J") (pinfunction "8_J") (pintype "bidirectional"))
      (node (ref "E23") (pin "6") (pinfunction "C_6") (pintype "input"))
    )
    (net (code "5") (name "BAC02") (class "Default")
      (node (ref "D36L1") (pin "N") (pinfunction "12_N") (pintype "bidirectional"))
      (node (ref "D36L2") (pin "N") (pinfunction "12_N") (pintype "bidirectional"))
      (node (ref "E23") (pin "5") (pinfunction "B_5") (pintype "input"))
    )
    (net (code "6") (name "BAC03") (class "Default")
      (node (ref "D36L1") (pin "T") (pinfunction "16_T") (pintype "bidirectional"))
      (node (ref "D36L2") (pin "T") (pinfunction "16_T") (pintype "bidirectional"))
      (node (ref "E23") (pin "4") (pinfunction "A_4") (pintype "input"))
    )
    (net (code "7") (name "BAC04") (class "Default")
      (node (ref "D36L1") (pin "X") (pinfunction "20_X") (pintype "bidirectional"))
      (node (ref "D36L2") (pin "X") (pinfunction "20_X") (pintype "bidirectional"))
      (node (ref "E16") (pin "12") (pinfunction "D_12") (pintype "input"))
      (node (ref "E21") (pin "7") (pinfunction "D_7") (pintype "input"))
    )
    (net (code "8") (name "BAC05") (class "Default")
      (node (ref "D36L1") (pin "BB") (pinfunction "24_BB") (pintype "bidirectional"))
      (node (ref "D36L2") (pin "BB") (pinfunction "24_BB") (pintype "bidirectional"))
      (node (ref "E16") (pin "2") (pinfunction "D_2") (pintype "input"))
      (node (ref "E21") (pin "6") (pinfunction "C_6") (pintype "input"))
    )
    (net (code "9") (name "BAC06") (class "Default")
      (node (ref "D36L1") (pin "FF") (pinfunction "28_FF") (pintype "bidirectional"))
      (node (ref "D36L2") (pin "FF") (pinfunction "28_FF") (pintype "bidirectional"))
      (node (ref "E21") (pin "5") (pinfunction "B_5") (pintype "input"))
    )
    (net (code "10") (name "BAC07") (class "Default")
      (node (ref "D36L1") (pin "LL") (pinfunction "32_LL") (pintype "bidirectional"))
      (node (ref "D36L2") (pin "LL") (pinfunction "32_LL") (pintype "bidirectional"))
      (node (ref "E21") (pin "4") (pinfunction "A_4") (pintype "input"))
    )
    (net (code "11") (name "BAC08") (class "Default")
      (node (ref "D36L1") (pin "RR") (pinfunction "36_RR") (pintype "bidirectional"))
      (node (ref "D36L2") (pin "RR") (pinfunction "36_RR") (pintype "bidirectional"))
      (node (ref "E22") (pin "7") (pinfunction "D_7") (pintype "input"))
    )
    (net (code "12") (name "BAC09") (class "Default")
      (node (ref "D36L1") (pin "F") (pinfunction "6_F") (pintype "bidirectional"))
      (node (ref "D36L2") (pin "F") (pinfunction "6_F") (pintype "bidirectional"))
      (node (ref "E22") (pin "6") (pinfunction "C_6") (pintype "input"))
    )
    (net (code "13") (name "BAC10") (class "Default")
      (node (ref "D36L1") (pin "L") (pinfunction "10_L") (pintype "bidirectional"))
      (node (ref "D36L2") (pin "L") (pinfunction "10_L") (pintype "bidirectional"))
      (node (ref "E22") (pin "5") (pinfunction "B_5") (pintype "input"))
    )
    (net (code "14") (name "BAC11") (class "Default")
      (node (ref "D36L1") (pin "R") (pinfunction "14_R") (pintype "bidirectional"))
      (node (ref "D36L2") (pin "R") (pinfunction "14_R") (pintype "bidirectional"))
      (node (ref "E22") (pin "4") (pinfunction "A_4") (pintype "input"))
      (node (ref "E30") (pin "2") (pinfunction "D_2") (pintype "input"))
    )
    (net (code "15") (name "BINIT") (class "Default")
      (node (ref "D36L1") (pin "TT") (pinfunction "38_TT") (pintype "bidirectional"))
      (node (ref "D36L2") (pin "TT") (pinfunction "38_TT") (pintype "bidirectional"))
      (node (ref "E1") (pin "3") (pinfunction "I0_3") (pintype "input"))
      (node (ref "LASTDEV") (pin "2") (pinfunction "2_2") (pintype "passive"))
    )
    (net (code "16") (name "BIOP1") (class "Default")
      (node (ref "D36L1") (pin "V") (pinfunction "18_V") (pintype "bidirectional"))
      (node (ref "D36L2") (pin "V") (pinfunction "18_V") (pintype "bidirectional"))
      (node (ref "E11") (pin "6") (pinfunction "G1_6") (pintype "input"))
      (node (ref "LASTDEV") (pin "7") (pinfunction "7_7") (pintype "passive"))
    )
    (net (code "17") (name "BIOP2") (class "Default")
      (node (ref "D36L1") (pin "Z") (pinfunction "22_Z") (pintype "bidirectional"))
      (node (ref "D36L2") (pin "Z") (pinfunction "22_Z") (pintype "bidirectional"))
      (node (ref "E12") (pin "6") (pinfunction "G1_6") (pintype "input"))
      (node (ref "LASTDEV") (pin "6") (pinfunction "6_6") (pintype "passive"))
    )
    (net (code "18") (name "BIOP4") (class "Default")
      (node (ref "D36L1") (pin "DD") (pinfunction "26_DD") (pintype "bidirectional"))
      (node (ref "D36L2") (pin "DD") (pinfunction "26_DD") (pintype "bidirectional"))
      (node (ref "E13") (pin "6") (pinfunction "G1_6") (pintype "input"))
      (node (ref "LASTDEV") (pin "5") (pinfunction "5_5") (pintype "passive"))
    )
    (net (code "19") (name "BMB00") (class "Default")
      (node (ref "D35L1") (pin "D") (pinfunction "4_D") (pintype "bidirectional"))
      (node (ref "D35L2") (pin "D") (pinfunction "4_D") (pintype "bidirectional"))
    )
    (net (code "20") (name "BMB01") (class "Default")
      (node (ref "D35L1") (pin "J") (pinfunction "8_J") (pintype "bidirectional"))
      (node (ref "D35L2") (pin "J") (pinfunction "8_J") (pintype "bidirectional"))
    )
    (net (code "21") (name "BMB02") (class "Default")
      (node (ref "D35L1") (pin "N") (pinfunction "12_N") (pintype "bidirectional"))
      (node (ref "D35L2") (pin "N") (pinfunction "12_N") (pintype "bidirectional"))
    )
    (net (code "22") (name "BMB03") (class "Default")
      (node (ref "D35L1") (pin "X") (pinfunction "20_X") (pintype "bidirectional"))
      (node (ref "D35L2") (pin "X") (pinfunction "20_X") (pintype "bidirectional"))
      (node (ref "E1") (pin "13") (pinfunction "I2_13") (pintype "input"))
    )
    (net (code "23") (name "BMB04") (class "Default")
      (node (ref "D35L1") (pin "FF") (pinfunction "28_FF") (pintype "bidirectional"))
      (node (ref "D35L2") (pin "FF") (pinfunction "28_FF") (pintype "bidirectional"))
      (node (ref "E1") (pin "2") (pinfunction "I1_2") (pintype "input"))
    )
    (net (code "24") (name "BMB05") (class "Default")
      (node (ref "D35L1") (pin "RR") (pinfunction "36_RR") (pintype "bidirectional"))
      (node (ref "D35L2") (pin "RR") (pinfunction "36_RR") (pintype "bidirectional"))
      (node (ref "E1") (pin "1") (pinfunction "I0_1") (pintype "input"))
    )
    (net (code "25") (name "BMB06") (class "Default")
      (node (ref "D35L1") (pin "L") (pinfunction "10_L") (pintype "bidirectional"))
      (node (ref "D35L2") (pin "L") (pinfunction "10_L") (pintype "bidirectional"))
      (node (ref "E14") (pin "3") (pinfunction "C_3") (pintype "input"))
    )
    (net (code "26") (name "BMB07") (class "Default")
      (node (ref "D35L1") (pin "V") (pinfunction "18_V") (pintype "bidirectional"))
      (node (ref "D35L2") (pin "V") (pinfunction "18_V") (pintype "bidirectional"))
      (node (ref "E14") (pin "2") (pinfunction "B_2") (pintype "input"))
    )
    (net (code "27") (name "BMB08") (class "Default")
      (node (ref "D35L1") (pin "DD") (pinfunction "26_DD") (pintype "bidirectional"))
      (node (ref "D35L2") (pin "DD") (pinfunction "26_DD") (pintype "bidirectional"))
      (node (ref "E14") (pin "1") (pinfunction "A_1") (pintype "input"))
    )
    (net (code "28") (name "BMB09") (class "Default")
      (node (ref "D35L1") (pin "JJ") (pinfunction "30_JJ") (pintype "bidirectional"))
      (node (ref "D35L2") (pin "JJ") (pinfunction "30_JJ") (pintype "bidirectional"))
      (node (ref "E11") (pin "3") (pinfunction "C_3") (pintype "input"))
      (node (ref "E12") (pin "3") (pinfunction "C_3") (pintype "input"))
      (node (ref "E13") (pin "3") (pinfunction "C_3") (pintype "input"))
    )
    (net (code "29") (name "BMB10") (class "Default")
      (node (ref "D35L1") (pin "NN") (pinfunction "34_NN") (pintype "bidirectional"))
      (node (ref "D35L2") (pin "NN") (pinfunction "34_NN") (pintype "bidirectional"))
      (node (ref "E11") (pin "2") (pinfunction "B_2") (pintype "input"))
      (node (ref "E12") (pin "2") (pinfunction "B_2") (pintype "input"))
      (node (ref "E13") (pin "2") (pinfunction "B_2") (pintype "input"))
    )
    (net (code "30") (name "BMB11") (class "Default")
      (node (ref "D35L1") (pin "TT") (pinfunction "38_TT") (pintype "bidirectional"))
      (node (ref "D35L2") (pin "TT") (pinfunction "38_TT") (pintype "bidirectional"))
      (node (ref "E11") (pin "1") (pinfunction "A_1") (pintype "input"))
      (node (ref "E12") (pin "1") (pinfunction "A_1") (pintype "input"))
      (node (ref "E13") (pin "1") (pinfunction "A_1") (pintype "input"))
    )
    (net (code "31") (name "BTS1") (class "Default")
      (node (ref "D36L1") (pin "NN") (pinfunction "34_NN") (pintype "bidirectional"))
      (node (ref "D36L2") (pin "NN") (pinfunction "34_NN") (pintype "bidirectional"))
      (node (ref "LASTDEV") (pin "3") (pinfunction "3_3") (pintype "passive"))
    )
    (net (code "32") (name "BTS3") (class "Default")
      (node (ref "D36L1") (pin "JJ") (pinfunction "30_JJ") (pintype "bidirectional"))
      (node (ref "D36L2") (pin "JJ") (pinfunction "30_JJ") (pintype "bidirectional"))
      (node (ref "LASTDEV") (pin "4") (pinfunction "4_4") (pintype "passive"))
    )
    (net (code "33") (name "CLK_BUF") (class "Default")
      (node (ref "E21") (pin "10") (pinfunction "CLK_10") (pintype "input"))
      (node (ref "E22") (pin "10") (pinfunction "CLK_10") (pintype "input"))
      (node (ref "E23") (pin "10") (pinfunction "CLK_10") (pintype "input"))
      (node (ref "E4") (pin "2") (pinfunction "CLK_2") (pintype "input"))
      (node (ref "E5") (pin "6") (pinfunction "O_6") (pintype "output"))
    )
    (net (code "34") (name "DONE") (class "Default")
      (node (ref "E17") (pin "4") (pinfunction "J_4") (pintype "input"))
      (node (ref "E20") (pin "13") (pinfunction "I1_13") (pintype "input"))
      (node (ref "E25") (pin "3") (pinfunction "I_3") (pintype "input"))
      (node (ref "E26") (pin "9") (pinfunction "I0_9") (pintype "input"))
      (node (ref "E31") (pin "4") (pinfunction "I2_4") (pintype "input"))
      (node (ref "E32") (pin "11") (pinfunction "I2_11") (pintype "input"))
      (node (ref "E36") (pin "10") (pinfunction "O_10") (pintype "output"))
    )
    (net (code "35") (name "DONE_FF") (class "Default")
      (node (ref "E17") (pin "15") (pinfunction "Q_15") (pintype "output"))
      (node (ref "IC10") (pin "6") (pinfunction "I0_6") (pintype "input"))
    )
    (net (code "36") (name "DONE_SKIP") (class "Default")
      (node (ref "E17") (pin "16") (pinfunction "K_16") (pintype "input"))
      (node (ref "E18") (pin "10") (pinfunction "O_10") (pintype "output"))
      (node (ref "E20") (pin "5") (pinfunction "I1_5") (pintype "input"))
      (node (ref "E26") (pin "10") (pinfunction "I1_10") (pintype "input"))
    )
    (net (code "37") (name "ERROR") (class "Default")
      (node (ref "E19") (pin "9") (pinfunction "J_9") (pintype "input"))
      (node (ref "E26") (pin "4") (pinfunction "I0_4") (pintype "input"))
      (node (ref "E36") (pin "1") (pinfunction "O_1") (pintype "output"))
    )
    (net (code "38") (name "ERR_SKIP") (class "Default")
      (node (ref "E18") (pin "4") (pinfunction "O_4") (pintype "output"))
      (node (ref "E19") (pin "12") (pinfunction "K_12") (pintype "input"))
      (node (ref "E20") (pin "4") (pinfunction "I0_4") (pintype "input"))
      (node (ref "E26") (pin "5") (pinfunction "I1_5") (pintype "input"))
    )
    (net (code "39") (name "GND") (class "Default")
      (node (ref "C1") (pin "2") (pinfunction "2_2") (pintype "passive"))
      (node (ref "C10") (pin "2") (pinfunction "2_2") (pintype "passive"))
      (node (ref "C11") (pin "2") (pinfunction "2_2") (pintype "passive"))
      (node (ref "C12") (pin "2") (pinfunction "2_2") (pintype "passive"))
      (node (ref "C13") (pin "2") (pinfunction "2_2") (pintype "passive"))
      (node (ref "C14") (pin "2") (pinfunction "2_2") (pintype "passive"))
      (node (ref "C15") (pin "2") (pinfunction "2_2") (pintype "passive"))
      (node (ref "C16") (pin "2") (pinfunction "2_2") (pintype "passive"))
      (node (ref "C17") (pin "2") (pinfunction "2_2") (pintype "passive"))
      (node (ref "C18") (pin "2") (pinfunction "2_2") (pintype "passive"))
      (node (ref "C19") (pin "2") (pinfunction "2_2") (pintype "passive"))
      (node (ref "C2") (pin "2") (pinfunction "2_2") (pintype "passive"))
      (node (ref "C20") (pin "2") (pinfunction "2_2") (pintype "passive"))
      (node (ref "C21") (pin "2") (pinfunction "2_2") (pintype "passive"))
      (node (ref "C22") (pin "2") (pinfunction "2_2") (pintype "passive"))
      (node (ref "C23") (pin "2") (pinfunction "2_2") (pintype "passive"))
      (node (ref "C24") (pin "2") (pinfunction "2_2") (pintype "passive"))
      (node (ref "C25") (pin "2") (pinfunction "2_2") (pintype "passive"))
      (node (ref "C26") (pin "2") (pinfunction "2_2") (pintype "passive"))
      (node (ref "C27") (pin "2") (pinfunction "2_2") (pintype "passive"))
      (node (ref "C28") (pin "2") (pinfunction "2_2") (pintype "passive"))
      (node (ref "C29") (pin "2") (pinfunction "2_2") (pintype "passive"))
      (node (ref "C3") (pin "2") (pinfunction "2_2") (pintype "passive"))
      (node (ref "C30") (pin "2") (pinfunction "2_2") (pintype "passive"))
      (node (ref "C31") (pin "2") (pinfunction "2_2") (pintype "passive"))
      (node (ref "C32") (pin "2") (pinfunction "2_2") (pintype "passive"))
      (node (ref "C33") (pin "2") (pinfunction "2_2") (pintype "passive"))
      (node (ref "C34") (pin "2") (pinfunction "2_2") (pintype "passive"))
      (node (ref "C35") (pin "2") (pinfunction "2_2") (pintype "passive"))
      (node (ref "C36") (pin "2") (pinfunction "2_2") (pintype "passive"))
      (node (ref "C37") (pin "2") (pinfunction "2_2") (pintype "passive"))
      (node (ref "C38") (pin "2") (pinfunction "2_2") (pintype "passive"))
      (node (ref "C39") (pin "2") (pinfunction "2_2") (pintype "passive"))
      (node (ref "C4") (pin "2") (pinfunction "2_2") (pintype "passive"))
      (node (ref "C40") (pin "-") (pinfunction "-_-") (pintype "passive"))
      (node (ref "C5") (pin "2") (pinfunction "2_2") (pintype "passive"))
      (node (ref "C6") (pin "2") (pinfunction "2_2") (pintype "passive"))
      (node (ref "C7") (pin "2") (pinfunction "2_2") (pintype "passive"))
      (node (ref "C8") (pin "2") (pinfunction "2_2") (pintype "passive"))
      (node (ref "C9") (pin "2") (pinfunction "2_2") (pintype "passive"))
      (node (ref "D34L1") (pin "A") (pinfunction "1_A") (pintype "bidirectional"))
      (node (ref "D34L1") (pin "AA") (pinfunction "23_AA") (pintype "bidirectional"))
      (node (ref "D34L1") (pin "C") (pinfunction "3_C") (pintype "bidirectional"))
      (node (ref "D34L1") (pin "CC") (pinfunction "25_CC") (pintype "bidirectional"))
      (node (ref "D34L1") (pin "E") (pinfunction "5_E") (pintype "bidirectional"))
      (node (ref "D34L1") (pin "EE") (pinfunction "27_EE") (pintype "bidirectional"))
      (node (ref "D34L1") (pin "H") (pinfunction "7_H") (pintype "bidirectional"))
      (node (ref "D34L1") (pin "HH") (pinfunction "29_HH") (pintype "bidirectional"))
      (node (ref "D34L1") (pin "K") (pinfunction "9_K") (pintype "bidirectional"))
      (node (ref "D34L1") (pin "KK") (pinfunction "31_KK") (pintype "bidirectional"))
      (node (ref "D34L1") (pin "M") (pinfunction "11_M") (pintype "bidirectional"))
      (node (ref "D34L1") (pin "MM") (pinfunction "33_MM") (pintype "bidirectional"))
      (node (ref "D34L1") (pin "P") (pinfunction "13_P") (pintype "bidirectional"))
      (node (ref "D34L1") (pin "PP") (pinfunction "35_PP") (pintype "bidirectional"))
      (node (ref "D34L1") (pin "S") (pinfunction "15_S") (pintype "bidirectional"))
      (node (ref "D34L1") (pin "SS") (pinfunction "37_SS") (pintype "bidirectional"))
      (node (ref "D34L1") (pin "U") (pinfunction "17_U") (pintype "bidirectional"))
      (node (ref "D34L1") (pin "UU") (pinfunction "39_UU") (pintype "bidirectional"))
      (node (ref "D34L1") (pin "W") (pinfunction "19_W") (pintype "bidirectional"))
      (node (ref "D34L1") (pin "Y") (pinfunction "21_Y") (pintype "bidirectional"))
      (node (ref "D34L2") (pin "A") (pinfunction "1_A") (pintype "bidirectional"))
      (node (ref "D34L2") (pin "AA") (pinfunction "23_AA") (pintype "bidirectional"))
      (node (ref "D34L2") (pin "C") (pinfunction "3_C") (pintype "bidirectional"))
      (node (ref "D34L2") (pin "CC") (pinfunction "25_CC") (pintype "bidirectional"))
      (node (ref "D34L2") (pin "E") (pinfunction "5_E") (pintype "bidirectional"))
      (node (ref "D34L2") (pin "EE") (pinfunction "27_EE") (pintype "bidirectional"))
      (node (ref "D34L2") (pin "H") (pinfunction "7_H") (pintype "bidirectional"))
      (node (ref "D34L2") (pin "HH") (pinfunction "29_HH") (pintype "bidirectional"))
      (node (ref "D34L2") (pin "K") (pinfunction "9_K") (pintype "bidirectional"))
      (node (ref "D34L2") (pin "KK") (pinfunction "31_KK") (pintype "bidirectional"))
      (node (ref "D34L2") (pin "M") (pinfunction "11_M") (pintype "bidirectional"))
      (node (ref "D34L2") (pin "MM") (pinfunction "33_MM") (pintype "bidirectional"))
      (node (ref "D34L2") (pin "P") (pinfunction "13_P") (pintype "bidirectional"))
      (node (ref "D34L2") (pin "PP") (pinfunction "35_PP") (pintype "bidirectional"))
      (node (ref "D34L2") (pin "S") (pinfunction "15_S") (pintype "bidirectional"))
      (node (ref "D34L2") (pin "SS") (pinfunction "37_SS") (pintype "bidirectional"))
      (node (ref "D34L2") (pin "U") (pinfunction "17_U") (pintype "bidirectional"))
      (node (ref "D34L2") (pin "UU") (pinfunction "39_UU") (pintype "bidirectional"))
      (node (ref "D34L2") (pin "W") (pinfunction "19_W") (pintype "bidirectional"))
      (node (ref "D34L2") (pin "Y") (pinfunction "21_Y") (pintype "bidirectional"))
      (node (ref "D35L1") (pin "A") (pinfunction "1_A") (pintype "bidirectional"))
      (node (ref "D35L1") (pin "AA") (pinfunction "23_AA") (pintype "bidirectional"))
      (node (ref "D35L1") (pin "C") (pinfunction "3_C") (pintype "bidirectional"))
      (node (ref "D35L1") (pin "CC") (pinfunction "25_CC") (pintype "bidirectional"))
      (node (ref "D35L1") (pin "E") (pinfunction "5_E") (pintype "bidirectional"))
      (node (ref "D35L1") (pin "EE") (pinfunction "27_EE") (pintype "bidirectional"))
      (node (ref "D35L1") (pin "H") (pinfunction "7_H") (pintype "bidirectional"))
      (node (ref "D35L1") (pin "HH") (pinfunction "29_HH") (pintype "bidirectional"))
      (node (ref "D35L1") (pin "K") (pinfunction "9_K") (pintype "bidirectional"))
      (node (ref "D35L1") (pin "KK") (pinfunction "31_KK") (pintype "bidirectional"))
      (node (ref "D35L1") (pin "M") (pinfunction "11_M") (pintype "bidirectional"))
      (node (ref "D35L1") (pin "MM") (pinfunction "33_MM") (pintype "bidirectional"))
      (node (ref "D35L1") (pin "P") (pinfunction "13_P") (pintype "bidirectional"))
      (node (ref "D35L1") (pin "PP") (pinfunction "35_PP") (pintype "bidirectional"))
      (node (ref "D35L1") (pin "S") (pinfunction "15_S") (pintype "bidirectional"))
      (node (ref "D35L1") (pin "SS") (pinfunction "37_SS") (pintype "bidirectional"))
      (node (ref "D35L1") (pin "U") (pinfunction "17_U") (pintype "bidirectional"))
      (node (ref "D35L1") (pin "UU") (pinfunction "39_UU") (pintype "bidirectional"))
      (node (ref "D35L1") (pin "W") (pinfunction "19_W") (pintype "bidirectional"))
      (node (ref "D35L1") (pin "Y") (pinfunction "21_Y") (pintype "bidirectional"))
      (node (ref "D35L2") (pin "A") (pinfunction "1_A") (pintype "bidirectional"))
      (node (ref "D35L2") (pin "AA") (pinfunction "23_AA") (pintype "bidirectional"))
      (node (ref "D35L2") (pin "C") (pinfunction "3_C") (pintype "bidirectional"))
      (node (ref "D35L2") (pin "CC") (pinfunction "25_CC") (pintype "bidirectional"))
      (node (ref "D35L2") (pin "E") (pinfunction "5_E") (pintype "bidirectional"))
      (node (ref "D35L2") (pin "EE") (pinfunction "27_EE") (pintype "bidirectional"))
      (node (ref "D35L2") (pin "H") (pinfunction "7_H") (pintype "bidirectional"))
      (node (ref "D35L2") (pin "HH") (pinfunction "29_HH") (pintype "bidirectional"))
      (node (ref "D35L2") (pin "K") (pinfunction "9_K") (pintype "bidirectional"))
      (node (ref "D35L2") (pin "KK") (pinfunction "31_KK") (pintype "bidirectional"))
      (node (ref "D35L2") (pin "M") (pinfunction "11_M") (pintype "bidirectional"))
      (node (ref "D35L2") (pin "MM") (pinfunction "33_MM") (pintype "bidirectional"))
      (node (ref "D35L2") (pin "P") (pinfunction "13_P") (pintype "bidirectional"))
      (node (ref "D35L2") (pin "PP") (pinfunction "35_PP") (pintype "bidirectional"))
      (node (ref "D35L2") (pin "S") (pinfunction "15_S") (pintype "bidirectional"))
      (node (ref "D35L2") (pin "SS") (pinfunction "37_SS") (pintype "bidirectional"))
      (node (ref "D35L2") (pin "U") (pinfunction "17_U") (pintype "bidirectional"))
      (node (ref "D35L2") (pin "UU") (pinfunction "39_UU") (pintype "bidirectional"))
      (node (ref "D35L2") (pin "W") (pinfunction "19_W") (pintype "bidirectional"))
      (node (ref "D35L2") (pin "Y") (pinfunction "21_Y") (pintype "bidirectional"))
      (node (ref "D36L1") (pin "A") (pinfunction "1_A") (pintype "bidirectional"))
      (node (ref "D36L1") (pin "AA") (pinfunction "23_AA") (pintype "bidirectional"))
      (node (ref "D36L1") (pin "C") (pinfunction "3_C") (pintype "bidirectional"))
      (node (ref "D36L1") (pin "CC") (pinfunction "25_CC") (pintype "bidirectional"))
      (node (ref "D36L1") (pin "E") (pinfunction "5_E") (pintype "bidirectional"))
      (node (ref "D36L1") (pin "EE") (pinfunction "27_EE") (pintype "bidirectional"))
      (node (ref "D36L1") (pin "H") (pinfunction "7_H") (pintype "bidirectional"))
      (node (ref "D36L1") (pin "HH") (pinfunction "29_HH") (pintype "bidirectional"))
      (node (ref "D36L1") (pin "K") (pinfunction "9_K") (pintype "bidirectional"))
      (node (ref "D36L1") (pin "KK") (pinfunction "31_KK") (pintype "bidirectional"))
      (node (ref "D36L1") (pin "M") (pinfunction "11_M") (pintype "bidirectional"))
      (node (ref "D36L1") (pin "MM") (pinfunction "33_MM") (pintype "bidirectional"))
      (node (ref "D36L1") (pin "P") (pinfunction "13_P") (pintype "bidirectional"))
      (node (ref "D36L1") (pin "PP") (pinfunction "35_PP") (pintype "bidirectional"))
      (node (ref "D36L1") (pin "S") (pinfunction "15_S") (pintype "bidirectional"))
      (node (ref "D36L1") (pin "SS") (pinfunction "37_SS") (pintype "bidirectional"))
      (node (ref "D36L1") (pin "U") (pinfunction "17_U") (pintype "bidirectional"))
      (node (ref "D36L1") (pin "UU") (pinfunction "39_UU") (pintype "bidirectional"))
      (node (ref "D36L1") (pin "W") (pinfunction "19_W") (pintype "bidirectional"))
      (node (ref "D36L1") (pin "Y") (pinfunction "21_Y") (pintype "bidirectional"))
      (node (ref "D36L2") (pin "A") (pinfunction "1_A") (pintype "bidirectional"))
      (node (ref "D36L2") (pin "AA") (pinfunction "23_AA") (pintype "bidirectional"))
      (node (ref "D36L2") (pin "C") (pinfunction "3_C") (pintype "bidirectional"))
      (node (ref "D36L2") (pin "CC") (pinfunction "25_CC") (pintype "bidirectional"))
      (node (ref "D36L2") (pin "E") (pinfunction "5_E") (pintype "bidirectional"))
      (node (ref "D36L2") (pin "EE") (pinfunction "27_EE") (pintype "bidirectional"))
      (node (ref "D36L2") (pin "H") (pinfunction "7_H") (pintype "bidirectional"))
      (node (ref "D36L2") (pin "HH") (pinfunction "29_HH") (pintype "bidirectional"))
      (node (ref "D36L2") (pin "K") (pinfunction "9_K") (pintype "bidirectional"))
      (node (ref "D36L2") (pin "KK") (pinfunction "31_KK") (pintype "bidirectional"))
      (node (ref "D36L2") (pin "M") (pinfunction "11_M") (pintype "bidirectional"))
      (node (ref "D36L2") (pin "MM") (pinfunction "33_MM") (pintype "bidirectional"))
      (node (ref "D36L2") (pin "P") (pinfunction "13_P") (pintype "bidirectional"))
      (node (ref "D36L2") (pin "PP") (pinfunction "35_PP") (pintype "bidirectional"))
      (node (ref "D36L2") (pin "S") (pinfunction "15_S") (pintype "bidirectional"))
      (node (ref "D36L2") (pin "SS") (pinfunction "37_SS") (pintype "bidirectional"))
      (node (ref "D36L2") (pin "U") (pinfunction "17_U") (pintype "bidirectional"))
      (node (ref "D36L2") (pin "UU") (pinfunction "39_UU") (pintype "bidirectional"))
      (node (ref "D36L2") (pin "W") (pinfunction "19_W") (pintype "bidirectional"))
      (node (ref "D36L2") (pin "Y") (pinfunction "21_Y") (pintype "bidirectional"))
      (node (ref "DRIVE") (pin "A") (pinfunction "1_A") (pintype "bidirectional"))
      (node (ref "DRIVE") (pin "AA") (pinfunction "23_AA") (pintype "bidirectional"))
      (node (ref "DRIVE") (pin "B") (pinfunction "2_B") (pintype "bidirectional"))
      (node (ref "DRIVE") (pin "C") (pinfunction "3_C") (pintype "bidirectional"))
      (node (ref "DRIVE") (pin "CC") (pinfunction "25_CC") (pintype "bidirectional"))
      (node (ref "DRIVE") (pin "DD") (pinfunction "26_DD") (pintype "bidirectional"))
      (node (ref "DRIVE") (pin "E") (pinfunction "5_E") (pintype "bidirectional"))
      (node (ref "DRIVE") (pin "EE") (pinfunction "27_EE") (pintype "bidirectional"))
      (node (ref "DRIVE") (pin "F") (pinfunction "6_F") (pintype "bidirectional"))
      (node (ref "DRIVE") (pin "H") (pinfunction "7_H") (pintype "bidirectional"))
      (node (ref "DRIVE") (pin "HH") (pinfunction "29_HH") (pintype "bidirectional"))
      (node (ref "DRIVE") (pin "JJ") (pinfunction "30_JJ") (pintype "bidirectional"))
      (node (ref "DRIVE") (pin "K") (pinfunction "9_K") (pintype "bidirectional"))
      (node (ref "DRIVE") (pin "KK") (pinfunction "31_KK") (pintype "bidirectional"))
      (node (ref "DRIVE") (pin "L") (pinfunction "10_L") (pintype "bidirectional"))
      (node (ref "DRIVE") (pin "M") (pinfunction "11_M") (pintype "bidirectional"))
      (node (ref "DRIVE") (pin "MM") (pinfunction "33_MM") (pintype "bidirectional"))
      (node (ref "DRIVE") (pin "NN") (pinfunction "34_NN") (pintype "bidirectional"))
      (node (ref "DRIVE") (pin "P") (pinfunction "13_P") (pintype "bidirectional"))
      (node (ref "DRIVE") (pin "PP") (pinfunction "35_PP") (pintype "bidirectional"))
      (node (ref "DRIVE") (pin "R") (pinfunction "14_R") (pintype "bidirectional"))
      (node (ref "DRIVE") (pin "S") (pinfunction "15_S") (pintype "bidirectional"))
      (node (ref "DRIVE") (pin "SS") (pinfunction "37_SS") (pintype "bidirectional"))
      (node (ref "DRIVE") (pin "TT") (pinfunction "38_TT") (pintype "bidirectional"))
      (node (ref "DRIVE") (pin "U") (pinfunction "17_U") (pintype "bidirectional"))
      (node (ref "DRIVE") (pin "UU") (pinfunction "39_UU") (pintype "bidirectional"))
      (node (ref "DRIVE") (pin "V") (pinfunction "18_V") (pintype "bidirectional"))
      (node (ref "DRIVE") (pin "VV") (pinfunction "40_VV") (pintype "bidirectional"))
      (node (ref "DRIVE") (pin "W") (pinfunction "19_W") (pintype "bidirectional"))
      (node (ref "DRIVE") (pin "Y") (pinfunction "21_Y") (pintype "bidirectional"))
      (node (ref "DRIVE") (pin "Z") (pinfunction "22_Z") (pintype "bidirectional"))
      (node (ref "E11") (pin "5") (pinfunction "G2B_5") (pintype "input"))
      (node (ref "E12") (pin "5") (pinfunction "G2B_5") (pintype "input"))
      (node (ref "E13") (pin "5") (pinfunction "G2B_5") (pintype "input"))
      (node (ref "E2") (pin "2") (pinfunction "D_2") (pintype "input"))
      (node (ref "E4") (pin "6") (pinfunction "D_6") (pintype "input"))
      (node (ref "LASTDEV") (pin "1") (pinfunction "1_1") (pintype "passive"))
      (node (ref "R10") (pin "1") (pinfunction "1_1") (pintype "passive"))
      (node (ref "R11") (pin "1") (pinfunction "1_1") (pintype "passive"))
      (node (ref "R12") (pin "1") (pinfunction "1_1") (pintype "passive"))
      (node (ref "R13") (pin "1") (pinfunction "1_1") (pintype "passive"))
      (node (ref "R14") (pin "1") (pinfunction "1_1") (pintype "passive"))
      (node (ref "R15") (pin "1") (pinfunction "1_1") (pintype "passive"))
      (node (ref "R16") (pin "1") (pinfunction "1_1") (pintype "passive"))
      (node (ref "R17") (pin "1") (pinfunction "1_1") (pintype "passive"))
      (node (ref "SL1") (pin "2") (pinfunction "S_2") (pintype "passive"))
      (node (ref "SL1") (pin "3") (pinfunction "S_3") (pintype "passive"))
    )
    (net (code "40") (name "INIT") (class "Default")
      (node (ref "E1") (pin "8") (pinfunction "O_8") (pintype "output"))
      (node (ref "E15") (pin "4") (pinfunction "I0_4") (pintype "input"))
      (node (ref "E15") (pin "5") (pinfunction "I1_5") (pintype "input"))
      (node (ref "E18") (pin "12") (pinfunction "I1_12") (pintype "input"))
      (node (ref "IC8") (pin "6") (pinfunction "I0_6") (pintype "input"))
      (node (ref "IC8") (pin "7") (pinfunction "I1_7") (pintype "input"))
    )
    (net (code "41") (name "MAINT") (class "Default")
      (node (ref "E16") (pin "9") (pinfunction "Q_9") (pintype "output"))
      (node (ref "E32") (pin "9") (pinfunction "I0_9") (pintype "input"))
      (node (ref "E35") (pin "3") (pinfunction "I1_3") (pintype "input"))
      (node (ref "E35") (pin "6") (pinfunction "I1_6") (pintype "input"))
      (node (ref "E35") (pin "9") (pinfunction "I1_9") (pintype "input"))
      (node (ref "E36") (pin "2") (pinfunction "I0_2") (pintype "input"))
      (node (ref "E36") (pin "6") (pinfunction "I1_6") (pintype "input"))
      (node (ref "E36") (pin "9") (pinfunction "I1_9") (pintype "input"))
    )
    (net (code "42") (name "MSB8") (class "Default")
      (node (ref "E21") (pin "12") (pinfunction "QD_12") (pintype "output"))
      (node (ref "E23") (pin "2") (pinfunction "J_2") (pintype "input"))
      (node (ref "E23") (pin "3") (pinfunction "K_3") (pintype "input"))
      (node (ref "E8") (pin "5") (pinfunction "I2_5") (pintype "input"))
      (node (ref "IC1") (pin "6") (pinfunction "I0_6") (pintype "input"))
    )
    (net (code "43") (name "MSB12") (class "Default")
      (node (ref "E23") (pin "12") (pinfunction "QD_12") (pintype "output"))
      (node (ref "E8") (pin "2") (pinfunction "I1_2") (pintype "input"))
      (node (ref "IC6") (pin "1") (pinfunction "I0_1") (pintype "input"))
    )
    (net (code "44") (name "Net-(70-P)") (class "Default")
      (node (ref "70") (pin "1") (pinfunction "P_1") (pintype "passive"))
      (node (ref "E14") (pin "15") (pinfunction "Y0_15") (pintype "output"))
    )
    (net (code "45") (name "Net-(71-P)") (class "Default")
      (node (ref "71") (pin "1") (pinfunction "P_1") (pintype "passive"))
      (node (ref "E14") (pin "14") (pinfunction "Y1_14") (pintype "output"))
    )
    (net (code "46") (name "Net-(72-P)") (class "Default")
      (node (ref "72") (pin "1") (pinfunction "P_1") (pintype "passive"))
      (node (ref "E14") (pin "13") (pinfunction "Y2_13") (pintype "output"))
    )
    (net (code "47") (name "Net-(73-P)") (class "Default")
      (node (ref "73") (pin "1") (pinfunction "P_1") (pintype "passive"))
      (node (ref "E14") (pin "12") (pinfunction "Y3_12") (pintype "output"))
    )
    (net (code "48") (name "Net-(74-P)") (class "Default")
      (node (ref "74") (pin "1") (pinfunction "P_1") (pintype "passive"))
      (node (ref "E14") (pin "11") (pinfunction "Y4_11") (pintype "output"))
    )
    (net (code "49") (name "Net-(75-P)") (class "Default")
      (node (ref "75") (pin "1") (pinfunction "P_1") (pintype "passive"))
      (node (ref "E14") (pin "10") (pinfunction "Y5_10") (pintype "output"))
    )
    (net (code "50") (name "Net-(76-P)") (class "Default")
      (node (ref "76") (pin "1") (pinfunction "P_1") (pintype "passive"))
      (node (ref "E14") (pin "9") (pinfunction "Y6_9") (pintype "output"))
    )
    (net (code "51") (name "Net-(77-P)") (class "Default")
      (node (ref "77") (pin "1") (pinfunction "P_1") (pintype "passive"))
      (node (ref "E14") (pin "7") (pinfunction "Y7_7") (pintype "output"))
    )
    (net (code "52") (name "Net-(E1B-O)") (class "Default")
      (node (ref "E1") (pin "10") (pinfunction "I1_10") (pintype "input"))
      (node (ref "E1") (pin "6") (pinfunction "O_6") (pintype "output"))
      (node (ref "E1") (pin "9") (pinfunction "I0_9") (pintype "input"))
      (node (ref "E2") (pin "1") (pinfunction "CLR_1") (pintype "input"))
    )
    (net (code "53") (name "Net-(E1C-I2)") (class "Default")
      (node (ref "E1") (pin "11") (pinfunction "I2_11") (pintype "input"))
      (node (ref "E2") (pin "6") (pinfunction "~{Q}_6") (pintype "output"))
    )
    (net (code "54") (name "Net-(E4A-A)") (class "Default")
      (node (ref "E4") (pin "10") (pinfunction "ENT_10") (pintype "input"))
      (node (ref "E4") (pin "3") (pinfunction "A_3") (pintype "input"))
      (node (ref "E4") (pin "4") (pinfunction "B_4") (pintype "input"))
      (node (ref "E4") (pin "7") (pinfunction "ENP_7") (pintype "input"))
      (node (ref "R19") (pin "2") (pinfunction "2_2") (pintype "passive"))
    )
    (net (code "55") (name "Net-(E4A-C)") (class "Default")
      (node (ref "E4") (pin "5") (pinfunction "C_5") (pintype "input"))
      (node (ref "E5") (pin "3") (pinfunction "O_3") (pintype "output"))
    )
    (net (code "56") (name "Net-(E5A-I0)") (class "Default")
      (node (ref "E5") (pin "1") (pinfunction "I0_1") (pintype "input"))
      (node (ref "E5") (pin "11") (pinfunction "O_11") (pintype "output"))
    )
    (net (code "57") (name "Net-(E8A-O)") (class "Default")
      (node (ref "E8") (pin "11") (pinfunction "I2_11") (pintype "input"))
      (node (ref "E8") (pin "12") (pinfunction "O_12") (pintype "output"))
    )
    (net (code "58") (name "Net-(E8B-O)") (class "Default")
      (node (ref "E8") (pin "6") (pinfunction "O_6") (pintype "output"))
      (node (ref "E8") (pin "9") (pinfunction "I0_9") (pintype "input"))
    )
    (net (code "59") (name "Net-(E10A-I0)") (class "Default")
      (node (ref "E10") (pin "1") (pinfunction "I0_1") (pintype "input"))
      (node (ref "E10") (pin "6") (pinfunction "O_6") (pintype "output"))
    )
    (net (code "60") (name "Net-(E10A-O)") (class "Default")
      (node (ref "E10") (pin "10") (pinfunction "I1_10") (pintype "input"))
      (node (ref "E10") (pin "11") (pinfunction "I2_11") (pintype "input"))
      (node (ref "E10") (pin "12") (pinfunction "O_12") (pintype "output"))
    )
    (net (code "61") (name "Net-(E10C-O)") (class "Default")
      (node (ref "E10") (pin "8") (pinfunction "O_8") (pintype "output"))
      (node (ref "IC7") (pin "1") (pinfunction "I0_1") (pintype "input"))
      (node (ref "IC7") (pin "2") (pinfunction "I1_2") (pintype "input"))
    )
    (net (code "62") (name "Net-(E14A-G2A)") (class "Default")
      (node (ref "E1") (pin "12") (pinfunction "O_12") (pintype "output"))
      (node (ref "E14") (pin "4") (pinfunction "G2A_4") (pintype "input"))
      (node (ref "E14") (pin "5") (pinfunction "G2B_5") (pintype "input"))
    )
    (net (code "63") (name "Net-(E15A-O)") (class "Default")
      (node (ref "E15") (pin "3") (pinfunction "O_3") (pintype "output"))
      (node (ref "E8") (pin "13") (pinfunction "I2_13") (pintype "input"))
      (node (ref "E8") (pin "3") (pinfunction "I0_3") (pintype "input"))
    )
    (net (code "64") (name "Net-(E15C-I0)") (class "Default")
      (node (ref "E15") (pin "9") (pinfunction "I0_9") (pintype "input"))
      (node (ref "E20") (pin "11") (pinfunction "O_11") (pintype "output"))
      (node (ref "E24") (pin "10") (pinfunction "I1_10") (pintype "input"))
    )
    (net (code "65") (name "Net-(E15C-O)") (class "Default")
      (node (ref "E15") (pin "8") (pinfunction "O_8") (pintype "output"))
      (node (ref "E24") (pin "12") (pinfunction "I0_12") (pintype "input"))
    )
    (net (code "66") (name "Net-(E15D-O)") (class "Default")
      (node (ref "E15") (pin "11") (pinfunction "O_11") (pintype "output"))
      (node (ref "E8") (pin "10") (pinfunction "I1_10") (pintype "input"))
    )
    (net (code "67") (name "Net-(E17A-CLK)") (class "Default")
      (node (ref "E17") (pin "1") (pinfunction "CLK_1") (pintype "input"))
      (node (ref "E26") (pin "8") (pinfunction "O_8") (pintype "output"))
    )
    (net (code "68") (name "Net-(E17A-~{Q})") (class "Default")
      (node (ref "E17") (pin "14") (pinfunction "~{Q}_14") (pintype "output"))
      (node (ref "E18") (pin "9") (pinfunction "I1_9") (pintype "input"))
    )
    (net (code "69") (name "Net-(E17B-CLR)") (class "Default")
      (node (ref "E17") (pin "8") (pinfunction "CLR_8") (pintype "input"))
      (node (ref "E18") (pin "13") (pinfunction "O_13") (pintype "output"))
    )
    (net (code "70") (name "Net-(E17B-J)") (class "Default")
      (node (ref "E17") (pin "12") (pinfunction "K_12") (pintype "input"))
      (node (ref "E17") (pin "9") (pinfunction "J_9") (pintype "input"))
      (node (ref "E8") (pin "8") (pinfunction "O_8") (pintype "output"))
      (node (ref "IC7") (pin "7") (pinfunction "I1_7") (pintype "input"))
    )
    (net (code "71") (name "Net-(E18A-I1)") (class "Default")
      (node (ref "E18") (pin "3") (pinfunction "I1_3") (pintype "input"))
      (node (ref "E19") (pin "14") (pinfunction "~{Q}_14") (pintype "output"))
    )
    (net (code "72") (name "Net-(E18B-I1)") (class "Default")
      (node (ref "E18") (pin "6") (pinfunction "I1_6") (pintype "input"))
      (node (ref "E19") (pin "10") (pinfunction "~{Q}_10") (pintype "output"))
    )
    (net (code "73") (name "Net-(E19A-CLK)") (class "Default")
      (node (ref "E19") (pin "1") (pinfunction "CLK_1") (pintype "input"))
      (node (ref "E26") (pin "3") (pinfunction "O_3") (pintype "output"))
    )
    (net (code "74") (name "Net-(E19B-CLK)") (class "Default")
      (node (ref "E19") (pin "6") (pinfunction "CLK_6") (pintype "input"))
      (node (ref "E26") (pin "6") (pinfunction "O_6") (pintype "output"))
    )
    (net (code "75") (name "Net-(E20A-I1)") (class "Default")
      (node (ref "E20") (pin "2") (pinfunction "I1_2") (pintype "input"))
      (node (ref "E20") (pin "6") (pinfunction "O_6") (pintype "output"))
    )
    (net (code "76") (name "Net-(E20A-O)") (class "Default")
      (node (ref "E20") (pin "3") (pinfunction "O_3") (pintype "output"))
      (node (ref "IC10") (pin "1") (pinfunction "I0_1") (pintype "input"))
      (node (ref "IC10") (pin "2") (pinfunction "I1_2") (pintype "input"))
    )
    (net (code "77") (name "Net-(E21A-J)") (class "Default")
      (node (ref "E21") (pin "2") (pinfunction "J_2") (pintype "input"))
      (node (ref "E21") (pin "3") (pinfunction "K_3") (pintype "input"))
      (node (ref "E22") (pin "12") (pinfunction "QD_12") (pintype "output"))
      (node (ref "IC4") (pin "6") (pinfunction "I0_6") (pintype "input"))
    )
    (net (code "78") (name "Net-(E21A-QA)") (class "Default")
      (node (ref "E21") (pin "15") (pinfunction "QA_15") (pintype "output"))
      (node (ref "IC3") (pin "6") (pinfunction "I0_6") (pintype "input"))
    )
    (net (code "79") (name "Net-(E21A-QB)") (class "Default")
      (node (ref "E21") (pin "14") (pinfunction "QB_14") (pintype "output"))
      (node (ref "IC3") (pin "1") (pinfunction "I0_1") (pintype "input"))
    )
    (net (code "80") (name "Net-(E21A-QC)") (class "Default")
      (node (ref "E21") (pin "13") (pinfunction "QC_13") (pintype "output"))
      (node (ref "IC4") (pin "1") (pinfunction "I0_1") (pintype "input"))
    )
    (net (code "81") (name "Net-(E22A-QA)") (class "Default")
      (node (ref "E22") (pin "15") (pinfunction "QA_15") (pintype "output"))
      (node (ref "IC2") (pin "1") (pinfunction "I0_1") (pintype "input"))
    )
    (net (code "82") (name "Net-(E22A-QB)") (class "Default")
      (node (ref "E22") (pin "14") (pinfunction "QB_14") (pintype "output"))
      (node (ref "IC5") (pin "6") (pinfunction "I0_6") (pintype "input"))
    )
    (net (code "83") (name "Net-(E22A-QC)") (class "Default")
      (node (ref "E22") (pin "13") (pinfunction "QC_13") (pintype "output"))
      (node (ref "IC5") (pin "1") (pinfunction "I0_1") (pintype "input"))
    )
    (net (code "84") (name "Net-(E23A-QA)") (class "Default")
      (node (ref "E23") (pin "15") (pinfunction "QA_15") (pintype "output"))
      (node (ref "IC2") (pin "6") (pinfunction "I0_6") (pintype "input"))
    )
    (net (code "85") (name "Net-(E23A-QB)") (class "Default")
      (node (ref "E23") (pin "14") (pinfunction "QB_14") (pintype "output"))
      (node (ref "IC1") (pin "1") (pinfunction "I0_1") (pintype "input"))
    )
    (net (code "86") (name "Net-(E23A-QC)") (class "Default")
      (node (ref "E23") (pin "13") (pinfunction "QC_13") (pintype "output"))
      (node (ref "IC6") (pin "6") (pinfunction "I0_6") (pintype "input"))
    )
    (net (code "87") (name "Net-(E24A-I1)") (class "Default")
      (node (ref "E24") (pin "2") (pinfunction "I1_2") (pintype "input"))
      (node (ref "E35") (pin "13") (pinfunction "O_13") (pintype "output"))
      (node (ref "IC1") (pin "7") (pinfunction "I1_7") (pintype "input"))
      (node (ref "IC2") (pin "2") (pinfunction "I1_2") (pintype "input"))
      (node (ref "IC3") (pin "2") (pinfunction "I1_2") (pintype "input"))
      (node (ref "IC3") (pin "7") (pinfunction "I1_7") (pintype "input"))
      (node (ref "IC4") (pin "2") (pinfunction "I1_2") (pintype "input"))
      (node (ref "IC4") (pin "7") (pinfunction "I1_7") (pintype "input"))
      (node (ref "IC5") (pin "2") (pinfunction "I1_2") (pintype "input"))
      (node (ref "IC5") (pin "7") (pinfunction "I1_7") (pintype "input"))
    )
    (net (code "88") (name "Net-(E24A-O)") (class "Default")
      (node (ref "E24") (pin "3") (pinfunction "O_3") (pintype "output"))
      (node (ref "IC1") (pin "2") (pinfunction "I1_2") (pintype "input"))
      (node (ref "IC2") (pin "7") (pinfunction "I1_7") (pintype "input"))
      (node (ref "IC6") (pin "2") (pinfunction "I1_2") (pintype "input"))
      (node (ref "IC6") (pin "7") (pinfunction "I1_7") (pintype "input"))
    )
    (net (code "89") (name "Net-(E24B-O)") (class "Default")
      (node (ref "E24") (pin "6") (pinfunction "O_6") (pintype "output"))
      (node (ref "E32") (pin "1") (pinfunction "I0_1") (pintype "input"))
    )
    (net (code "90") (name "Net-(E24C-O)") (class "Default")
      (node (ref "E24") (pin "8") (pinfunction "O_8") (pintype "output"))
      (node (ref "E30") (pin "13") (pinfunction "CLR_13") (pintype "input"))
    )
    (net (code "91") (name "Net-(E25C-O)") (class "Default")
      (node (ref "E25") (pin "6") (pinfunction "O_6") (pintype "output"))
      (node (ref "E31") (pin "1") (pinfunction "I0_1") (pintype "input"))
      (node (ref "E31") (pin "2") (pinfunction "I1_2") (pintype "input"))
    )
    (net (code "92") (name "Net-(E25D-O)") (class "Default")
      (node (ref "E25") (pin "8") (pinfunction "O_8") (pintype "output"))
      (node (ref "E31") (pin "13") (pinfunction "I3_13") (pintype "input"))
    )
    (net (code "93") (name "Net-(E25E-O)") (class "Default")
      (node (ref "E25") (pin "10") (pinfunction "O_10") (pintype "output"))
      (node (ref "E26") (pin "12") (pinfunction "I0_12") (pintype "input"))
      (node (ref "E26") (pin "13") (pinfunction "I1_13") (pintype "input"))
    )
    (net (code "94") (name "Net-(E25F-O)") (class "Default")
      (node (ref "E25") (pin "12") (pinfunction "O_12") (pintype "output"))
      (node (ref "E36") (pin "11") (pinfunction "I0_11") (pintype "input"))
      (node (ref "E36") (pin "12") (pinfunction "I1_12") (pintype "input"))
    )
    (net (code "95") (name "Net-(E30A-Q)") (class "Default")
      (node (ref "E30") (pin "5") (pinfunction "Q_5") (pintype "output"))
      (node (ref "IC10") (pin "7") (pinfunction "I1_7") (pintype "input"))
    )
    (net (code "96") (name "Net-(E30B-CLK)") (class "Default")
      (node (ref "E30") (pin "11") (pinfunction "CLK_11") (pintype "input"))
      (node (ref "IC9") (pin "3") (pinfunction "O_3") (pintype "open_collector"))
      (node (ref "R18") (pin "1") (pinfunction "1_1") (pintype "passive"))
    )
    (net (code "97") (name "Net-(E31A-O)") (class "Default")
      (node (ref "E31") (pin "6") (pinfunction "O_6") (pintype "output"))
      (node (ref "IC9") (pin "1") (pinfunction "I0_1") (pintype "input"))
    )
    (net (code "98") (name "Net-(E31B-O)") (class "Default")
      (node (ref "E31") (pin "8") (pinfunction "O_8") (pintype "output"))
      (node (ref "IC9") (pin "2") (pinfunction "I1_2") (pintype "input"))
    )
    (net (code "99") (name "Net-(E32A-O)") (class "Default")
      (node (ref "E32") (pin "12") (pinfunction "O_12") (pintype "output"))
      (node (ref "E32") (pin "4") (pinfunction "I1_4") (pintype "input"))
      (node (ref "E32") (pin "5") (pinfunction "I2_5") (pintype "input"))
    )
    (net (code "100") (name "Net-(E32C-O)") (class "Default")
      (node (ref "E32") (pin "8") (pinfunction "O_8") (pintype "output"))
      (node (ref "E35") (pin "11") (pinfunction "I0_11") (pintype "input"))
    )
    (net (code "101") (name "Net-(PAD10-P)") (class "Default")
      (node (ref "E38") (pin "1") (pinfunction "1_1") (pintype "passive"))
      (node (ref "PAD10") (pin "1") (pinfunction "P_1") (pintype "passive"))
    )
    (net (code "102") (name "Net-(PAD11-P)") (class "Default")
      (node (ref "E38") (pin "2") (pinfunction "2_2") (pintype "passive"))
      (node (ref "PAD11") (pin "1") (pinfunction "P_1") (pintype "passive"))
    )
    (net (code "103") (name "Net-(PAD12-P)") (class "Default")
      (node (ref "E38") (pin "3") (pinfunction "3_3") (pintype "passive"))
      (node (ref "PAD12") (pin "1") (pinfunction "P_1") (pintype "passive"))
    )
    (net (code "104") (name "Net-(PAD13-P)") (class "Default")
      (node (ref "E38") (pin "4") (pinfunction "4_4") (pintype "passive"))
      (node (ref "PAD13") (pin "1") (pinfunction "P_1") (pintype "passive"))
    )
    (net (code "105") (name "Net-(PAD14-P)") (class "Default")
      (node (ref "E38") (pin "5") (pinfunction "5_5") (pintype "passive"))
      (node (ref "PAD14") (pin "1") (pinfunction "P_1") (pintype "passive"))
    )
    (net (code "106") (name "Net-(PAD15-P)") (class "Default")
      (node (ref "E38") (pin "6") (pinfunction "6_6") (pintype "passive"))
      (node (ref "PAD15") (pin "1") (pinfunction "P_1") (pintype "passive"))
    )
    (net (code "107") (name "Net-(PAD16-P)") (class "Default")
      (node (ref "E38") (pin "7") (pinfunction "7_7") (pintype "passive"))
      (node (ref "PAD16") (pin "1") (pinfunction "P_1") (pintype "passive"))
    )
    (net (code "108") (name "Net-(PAD17-P)") (class "Default")
      (node (ref "E38") (pin "8") (pinfunction "8_8") (pintype "passive"))
      (node (ref "PAD17") (pin "1") (pinfunction "P_1") (pintype "passive"))
    )
    (net (code "109") (name "Net-(PAD18-P)") (class "Default")
      (node (ref "E40") (pin "1") (pinfunction "1_1") (pintype "passive"))
      (node (ref "PAD18") (pin "1") (pinfunction "P_1") (pintype "passive"))
    )
    (net (code "110") (name "Net-(PAD19-P)") (class "Default")
      (node (ref "E40") (pin "2") (pinfunction "2_2") (pintype "passive"))
      (node (ref "PAD19") (pin "1") (pinfunction "P_1") (pintype "passive"))
    )
    (net (code "111") (name "Net-(PAD20-P)") (class "Default")
      (node (ref "E38") (pin "16") (pinfunction "16_16") (pintype "passive"))
      (node (ref "PAD20") (pin "1") (pinfunction "P_1") (pintype "passive"))
    )
    (net (code "112") (name "Net-(PAD21-P)") (class "Default")
      (node (ref "E38") (pin "15") (pinfunction "15_15") (pintype "passive"))
      (node (ref "PAD21") (pin "1") (pinfunction "P_1") (pintype "passive"))
    )
    (net (code "113") (name "Net-(PAD22-P)") (class "Default")
      (node (ref "E38") (pin "14") (pinfunction "14_14") (pintype "passive"))
      (node (ref "PAD22") (pin "1") (pinfunction "P_1") (pintype "passive"))
    )
    (net (code "114") (name "Net-(PAD23-P)") (class "Default")
      (node (ref "E38") (pin "13") (pinfunction "13_13") (pintype "passive"))
      (node (ref "PAD23") (pin "1") (pinfunction "P_1") (pintype "passive"))
    )
    (net (code "115") (name "Net-(PAD24-P)") (class "Default")
      (node (ref "E38") (pin "12") (pinfunction "12_12") (pintype "passive"))
      (node (ref "PAD24") (pin "1") (pinfunction "P_1") (pintype "passive"))
    )
    (net (code "116") (name "Net-(PAD25-P)") (class "Default")
      (node (ref "E38") (pin "11") (pinfunction "11_11") (pintype "passive"))
      (node (ref "PAD25") (pin "1") (pinfunction "P_1") (pintype "passive"))
    )
    (net (code "117") (name "Net-(PAD26-P)") (class "Default")
      (node (ref "E38") (pin "10") (pinfunction "10_10") (pintype "passive"))
      (node (ref "PAD26") (pin "1") (pinfunction "P_1") (pintype "passive"))
    )
    (net (code "118") (name "Net-(PAD27-P)") (class "Default")
      (node (ref "E38") (pin "9") (pinfunction "9_9") (pintype "passive"))
      (node (ref "PAD27") (pin "1") (pinfunction "P_1") (pintype "passive"))
    )
    (net (code "119") (name "Net-(PAD28-P)") (class "Default")
      (node (ref "E40") (pin "3") (pinfunction "3_3") (pintype "passive"))
      (node (ref "PAD28") (pin "1") (pinfunction "P_1") (pintype "passive"))
    )
    (net (code "120") (name "Net-(PAD29-P)") (class "Default")
      (node (ref "E40") (pin "4") (pinfunction "4_4") (pintype "passive"))
      (node (ref "PAD29") (pin "1") (pinfunction "P_1") (pintype "passive"))
    )
    (net (code "121") (name "Net-(PAD30-P)") (class "Default")
      (node (ref "E40") (pin "5") (pinfunction "5_5") (pintype "passive"))
      (node (ref "PAD30") (pin "1") (pinfunction "P_1") (pintype "passive"))
    )
    (net (code "122") (name "Net-(PAD31-P)") (class "Default")
      (node (ref "E40") (pin "6") (pinfunction "6_6") (pintype "passive"))
      (node (ref "PAD31") (pin "1") (pinfunction "P_1") (pintype "passive"))
    )
    (net (code "123") (name "Net-(PAD32-P)") (class "Default")
      (node (ref "E40") (pin "7") (pinfunction "7_7") (pintype "passive"))
      (node (ref "PAD32") (pin "1") (pinfunction "P_1") (pintype "passive"))
    )
    (net (code "124") (name "Net-(PAD33-P)") (class "Default")
      (node (ref "E40") (pin "8") (pinfunction "8_8") (pintype "passive"))
      (node (ref "PAD33") (pin "1") (pinfunction "P_1") (pintype "passive"))
    )
    (net (code "125") (name "Net-(PAD34-P)") (class "Default")
      (node (ref "E40") (pin "16") (pinfunction "16_16") (pintype "passive"))
      (node (ref "PAD34") (pin "1") (pinfunction "P_1") (pintype "passive"))
    )
    (net (code "126") (name "Net-(PAD35-P)") (class "Default")
      (node (ref "E40") (pin "15") (pinfunction "15_15") (pintype "passive"))
      (node (ref "PAD35") (pin "1") (pinfunction "P_1") (pintype "passive"))
    )
    (net (code "127") (name "Net-(PAD36-P)") (class "Default")
      (node (ref "E40") (pin "14") (pinfunction "14_14") (pintype "passive"))
      (node (ref "PAD36") (pin "1") (pinfunction "P_1") (pintype "passive"))
    )
    (net (code "128") (name "Net-(PAD37-P)") (class "Default")
      (node (ref "E40") (pin "13") (pinfunction "13_13") (pintype "passive"))
      (node (ref "PAD37") (pin "1") (pinfunction "P_1") (pintype "passive"))
    )
    (net (code "129") (name "Net-(PAD38-P)") (class "Default")
      (node (ref "E40") (pin "12") (pinfunction "12_12") (pintype "passive"))
      (node (ref "PAD38") (pin "1") (pinfunction "P_1") (pintype "passive"))
    )
    (net (code "130") (name "Net-(PAD39-P)") (class "Default")
      (node (ref "E40") (pin "11") (pinfunction "11_11") (pintype "passive"))
      (node (ref "PAD39") (pin "1") (pinfunction "P_1") (pintype "passive"))
    )
    (net (code "131") (name "Net-(PAD40-P)") (class "Default")
      (node (ref "E40") (pin "10") (pinfunction "10_10") (pintype "passive"))
      (node (ref "PAD40") (pin "1") (pinfunction "P_1") (pintype "passive"))
    )
    (net (code "132") (name "Net-(PAD41-P)") (class "Default")
      (node (ref "E40") (pin "9") (pinfunction "9_9") (pintype "passive"))
      (node (ref "PAD41") (pin "1") (pinfunction "P_1") (pintype "passive"))
    )
    (net (code "133") (name "Net-(PAD42-P)") (class "Default")
      (node (ref "E39") (pin "1") (pinfunction "1_1") (pintype "passive"))
      (node (ref "PAD42") (pin "1") (pinfunction "P_1") (pintype "passive"))
    )
    (net (code "134") (name "Net-(PAD43-P)") (class "Default")
      (node (ref "E39") (pin "2") (pinfunction "2_2") (pintype "passive"))
      (node (ref "PAD43") (pin "1") (pinfunction "P_1") (pintype "passive"))
    )
    (net (code "135") (name "Net-(PAD44-P)") (class "Default")
      (node (ref "E39") (pin "3") (pinfunction "3_3") (pintype "passive"))
      (node (ref "PAD44") (pin "1") (pinfunction "P_1") (pintype "passive"))
    )
    (net (code "136") (name "Net-(PAD45-P)") (class "Default")
      (node (ref "E39") (pin "4") (pinfunction "4_4") (pintype "passive"))
      (node (ref "PAD45") (pin "1") (pinfunction "P_1") (pintype "passive"))
    )
    (net (code "137") (name "Net-(PAD46-P)") (class "Default")
      (node (ref "E39") (pin "5") (pinfunction "5_5") (pintype "passive"))
      (node (ref "PAD46") (pin "1") (pinfunction "P_1") (pintype "passive"))
    )
    (net (code "138") (name "Net-(PAD47-P)") (class "Default")
      (node (ref "E39") (pin "6") (pinfunction "6_6") (pintype "passive"))
      (node (ref "PAD47") (pin "1") (pinfunction "P_1") (pintype "passive"))
    )
    (net (code "139") (name "Net-(PAD48-P)") (class "Default")
      (node (ref "E39") (pin "7") (pinfunction "7_7") (pintype "passive"))
      (node (ref "PAD48") (pin "1") (pinfunction "P_1") (pintype "passive"))
    )
    (net (code "140") (name "Net-(PAD49-P)") (class "Default")
      (node (ref "E39") (pin "8") (pinfunction "8_8") (pintype "passive"))
      (node (ref "PAD49") (pin "1") (pinfunction "P_1") (pintype "passive"))
    )
    (net (code "141") (name "Net-(PAD50-P)") (class "Default")
      (node (ref "E39") (pin "16") (pinfunction "16_16") (pintype "passive"))
      (node (ref "PAD50") (pin "1") (pinfunction "P_1") (pintype "passive"))
    )
    (net (code "142") (name "Net-(PAD51-P)") (class "Default")
      (node (ref "E39") (pin "15") (pinfunction "15_15") (pintype "passive"))
      (node (ref "PAD51") (pin "1") (pinfunction "P_1") (pintype "passive"))
    )
    (net (code "143") (name "Net-(PAD52-P)") (class "Default")
      (node (ref "E39") (pin "14") (pinfunction "14_14") (pintype "passive"))
      (node (ref "PAD52") (pin "1") (pinfunction "P_1") (pintype "passive"))
    )
    (net (code "144") (name "Net-(PAD53-P)") (class "Default")
      (node (ref "E39") (pin "13") (pinfunction "13_13") (pintype "passive"))
      (node (ref "PAD53") (pin "1") (pinfunction "P_1") (pintype "passive"))
    )
    (net (code "145") (name "Net-(PAD54-P)") (class "Default")
      (node (ref "E39") (pin "12") (pinfunction "12_12") (pintype "passive"))
      (node (ref "PAD54") (pin "1") (pinfunction "P_1") (pintype "passive"))
    )
    (net (code "146") (name "Net-(PAD55-P)") (class "Default")
      (node (ref "E39") (pin "11") (pinfunction "11_11") (pintype "passive"))
      (node (ref "PAD55") (pin "1") (pinfunction "P_1") (pintype "passive"))
    )
    (net (code "147") (name "Net-(PAD56-P)") (class "Default")
      (node (ref "E39") (pin "10") (pinfunction "10_10") (pintype "passive"))
      (node (ref "PAD56") (pin "1") (pinfunction "P_1") (pintype "passive"))
    )
    (net (code "148") (name "Net-(PAD57-P)") (class "Default")
      (node (ref "E39") (pin "9") (pinfunction "9_9") (pintype "passive"))
      (node (ref "PAD57") (pin "1") (pinfunction "P_1") (pintype "passive"))
    )
    (net (code "149") (name "PARITY") (class "Default")
      (node (ref "E15") (pin "1") (pinfunction "I0_1") (pintype "input"))
      (node (ref "E15") (pin "13") (pinfunction "I1_13") (pintype "input"))
      (node (ref "E15") (pin "2") (pinfunction "I1_2") (pintype "input"))
      (node (ref "E4") (pin "15") (pinfunction "RCO_15") (pintype "output"))
    )
    (net (code "150") (name "RD") (class "Default")
      (node (ref "E25") (pin "1") (pinfunction "I_1") (pintype "input"))
      (node (ref "E32") (pin "10") (pinfunction "I1_10") (pintype "input"))
      (node (ref "E35") (pin "10") (pinfunction "O_10") (pintype "output"))
    )
    (net (code "151") (name "RUN") (class "Default")
      (node (ref "E18") (pin "11") (pinfunction "I0_11") (pintype "input"))
      (node (ref "E30") (pin "9") (pinfunction "Q_9") (pintype "output"))
      (node (ref "IC9") (pin "6") (pinfunction "I0_6") (pintype "input"))
      (node (ref "IC9") (pin "7") (pinfunction "I1_7") (pintype "input"))
    )
    (net (code "152") (name "RX_DATA") (class "Default")
      (node (ref "E22") (pin "2") (pinfunction "J_2") (pintype "input"))
      (node (ref "E22") (pin "3") (pinfunction "K_3") (pintype "input"))
      (node (ref "E35") (pin "1") (pinfunction "O_1") (pintype "output"))
    )
    (net (code "153") (name "SHIFT") (class "Default")
      (node (ref "E32") (pin "3") (pinfunction "I0_3") (pintype "input"))
      (node (ref "E35") (pin "4") (pinfunction "O_4") (pintype "output"))
    )
    (net (code "154") (name "TR_SKIP") (class "Default")
      (node (ref "E18") (pin "1") (pinfunction "O_1") (pintype "output"))
      (node (ref "E19") (pin "16") (pinfunction "K_16") (pintype "input"))
      (node (ref "E20") (pin "1") (pinfunction "I0_1") (pintype "input"))
      (node (ref "E26") (pin "2") (pinfunction "I1_2") (pintype "input"))
    )
    (net (code "155") (name "VCC") (class "Default")
      (node (ref "C1") (pin "1") (pinfunction "1_1") (pintype "passive"))
      (node (ref "C10") (pin "1") (pinfunction "1_1") (pintype "passive"))
      (node (ref "C11") (pin "1") (pinfunction "1_1") (pintype "passive"))
      (node (ref "C12") (pin "1") (pinfunction "1_1") (pintype "passive"))
      (node (ref "C13") (pin "1") (pinfunction "1_1") (pintype "passive"))
      (node (ref "C14") (pin "1") (pinfunction "1_1") (pintype "passive"))
      (node (ref "C15") (pin "1") (pinfunction "1_1") (pintype "passive"))
      (node (ref "C16") (pin "1") (pinfunction "1_1") (pintype "passive"))
      (node (ref "C17") (pin "1") (pinfunction "1_1") (pintype "passive"))
      (node (ref "C18") (pin "1") (pinfunction "1_1") (pintype "passive"))
      (node (ref "C19") (pin "1") (pinfunction "1_1") (pintype "passive"))
      (node (ref "C2") (pin "1") (pinfunction "1_1") (pintype "passive"))
      (node (ref "C20") (pin "1") (pinfunction "1_1") (pintype "passive"))
      (node (ref "C21") (pin "1") (pinfunction "1_1") (pintype "passive"))
      (node (ref "C22") (pin "1") (pinfunction "1_1") (pintype "passive"))
      (node (ref "C23") (pin "1") (pinfunction "1_1") (pintype "passive"))
      (node (ref "C24") (pin "1") (pinfunction "1_1") (pintype "passive"))
      (node (ref "C25") (pin "1") (pinfunction "1_1") (pintype "passive"))
      (node (ref "C26") (pin "1") (pinfunction "1_1") (pintype "passive"))
      (node (ref "C27") (pin "1") (pinfunction "1_1") (pintype "passive"))
      (node (ref "C28") (pin "1") (pinfunction "1_1") (pintype "passive"))
      (node (ref "C29") (pin "1") (pinfunction "1_1") (pintype "passive"))
      (node (ref "C3") (pin "1") (pinfunction "1_1") (pintype "passive"))
      (node (ref "C30") (pin "1") (pinfunction "1_1") (pintype "passive"))
      (node (ref "C31") (pin "1") (pinfunction "1_1") (pintype "passive"))
      (node (ref "C32") (pin "1") (pinfunction "1_1") (pintype "passive"))
      (node (ref "C33") (pin "1") (pinfunction "1_1") (pintype "passive"))
      (node (ref "C34") (pin "1") (pinfunction "1_1") (pintype "passive"))
      (node (ref "C35") (pin "1") (pinfunction "1_1") (pintype "passive"))
      (node (ref "C36") (pin "1") (pinfunction "1_1") (pintype "passive"))
      (node (ref "C37") (pin "1") (pinfunction "1_1") (pintype "passive"))
      (node (ref "C38") (pin "1") (pinfunction "1_1") (pintype "passive"))
      (node (ref "C39") (pin "1") (pinfunction "1_1") (pintype "passive"))
      (node (ref "C4") (pin "1") (pinfunction "1_1") (pintype "passive"))
      (node (ref "C40") (pin "+") (pinfunction "+_+") (pintype "passive"))
      (node (ref "C5") (pin "1") (pinfunction "1_1") (pintype "passive"))
      (node (ref "C6") (pin "1") (pinfunction "1_1") (pintype "passive"))
      (node (ref "C7") (pin "1") (pinfunction "1_1") (pintype "passive"))
      (node (ref "C8") (pin "1") (pinfunction "1_1") (pintype "passive"))
      (node (ref "C9") (pin "1") (pinfunction "1_1") (pintype "passive"))
      (node (ref "E1") (pin "4") (pinfunction "I1_4") (pintype "input"))
      (node (ref "E1") (pin "5") (pinfunction "I2_5") (pintype "input"))
      (node (ref "E14") (pin "6") (pinfunction "G1_6") (pintype "input"))
      (node (ref "E16") (pin "10") (pinfunction "PRE_10") (pintype "input"))
      (node (ref "E16") (pin "4") (pinfunction "PRE_4") (pintype "input"))
      (node (ref "E17") (pin "7") (pinfunction "PRE_7") (pintype "input"))
      (node (ref "E2") (pin "10") (pinfunction "PRE_10") (pintype "input"))
      (node (ref "E2") (pin "11") (pinfunction "CLK_11") (pintype "input"))
      (node (ref "E2") (pin "12") (pinfunction "D_12") (pintype "input"))
      (node (ref "E2") (pin "13") (pinfunction "CLR_13") (pintype "input"))
      (node (ref "E20") (pin "10") (pinfunction "I1_10") (pintype "input"))
      (node (ref "E20") (pin "9") (pinfunction "I0_9") (pintype "input"))
      (node (ref "E25") (pin "11") (pinfunction "I_11") (pintype "input"))
      (node (ref "E25") (pin "13") (pinfunction "I_13") (pintype "input"))
      (node (ref "E30") (pin "10") (pinfunction "PRE_10") (pintype "input"))
      (node (ref "E30") (pin "12") (pinfunction "D_12") (pintype "input"))
      (node (ref "E30") (pin "4") (pinfunction "PRE_4") (pintype "input"))
      (node (ref "R1") (pin "2") (pinfunction "2_2") (pintype "passive"))
      (node (ref "R18") (pin "2") (pinfunction "2_2") (pintype "passive"))
      (node (ref "R19") (pin "1") (pinfunction "1_1") (pintype "passive"))
      (node (ref "R2") (pin "2") (pinfunction "2_2") (pintype "passive"))
      (node (ref "R20") (pin "2") (pinfunction "2_2") (pintype "passive"))
      (node (ref "R3") (pin "2") (pinfunction "2_2") (pintype "passive"))
      (node (ref "R4") (pin "2") (pinfunction "2_2") (pintype "passive"))
      (node (ref "R5") (pin "2") (pinfunction "2_2") (pintype "passive"))
      (node (ref "R6") (pin "2") (pinfunction "2_2") (pintype "passive"))
      (node (ref "R7") (pin "2") (pinfunction "2_2") (pintype "passive"))
      (node (ref "R8") (pin "2") (pinfunction "2_2") (pintype "passive"))
      (node (ref "R9") (pin "2") (pinfunction "2_2") (pintype "passive"))
      (node (ref "SL1") (pin "1") (pinfunction "S_1") (pintype "passive"))
    )
    (net (code "156") (name "WRT") (class "Default")
      (node (ref "E10") (pin "5") (pinfunction "I2_5") (pintype "input"))
      (node (ref "E15") (pin "10") (pinfunction "I1_10") (pintype "input"))
      (node (ref "E25") (pin "2") (pinfunction "O_2") (pintype "output"))
      (node (ref "IC7") (pin "6") (pinfunction "I0_6") (pintype "input"))
    )
    (net (code "157") (name "XDR2") (class "Default")
      (node (ref "E10") (pin "2") (pinfunction "I1_2") (pintype "input"))
      (node (ref "E5") (pin "12") (pinfunction "I0_12") (pintype "input"))
      (node (ref "E5") (pin "8") (pinfunction "O_8") (pintype "output"))
    )
    (net (code "158") (name "XFER_REQ") (class "Default")
      (node (ref "E19") (pin "4") (pinfunction "J_4") (pintype "input"))
      (node (ref "E20") (pin "12") (pinfunction "I0_12") (pintype "input"))
      (node (ref "E26") (pin "1") (pinfunction "I0_1") (pintype "input"))
      (node (ref "E36") (pin "4") (pinfunction "O_4") (pintype "output"))
    )
    (net (code "159") (name "unconnected-(D34L1-2-PadB)") (class "Default")
      (node (ref "D34L1") (pin "B") (pinfunction "2_B") (pintype "bidirectional"))
    )
    (net (code "160") (name "unconnected-(D34L1-34-PadNN)") (class "Default")
      (node (ref "D34L1") (pin "NN") (pinfunction "34_NN") (pintype "bidirectional"))
    )
    (net (code "161") (name "unconnected-(D34L1-38-PadTT)") (class "Default")
      (node (ref "D34L1") (pin "TT") (pinfunction "38_TT") (pintype "bidirectional"))
    )
    (net (code "162") (name "unconnected-(D34L1-40-PadVV)") (class "Default")
      (node (ref "D34L1") (pin "VV") (pinfunction "40_VV") (pintype "bidirectional"))
    )
    (net (code "163") (name "unconnected-(D34L2-2-PadB)") (class "Default")
      (node (ref "D34L2") (pin "B") (pinfunction "2_B") (pintype "bidirectional"))
    )
    (net (code "164") (name "unconnected-(D34L2-34-PadNN)") (class "Default")
      (node (ref "D34L2") (pin "NN") (pinfunction "34_NN") (pintype "bidirectional"))
    )
    (net (code "165") (name "unconnected-(D34L2-38-PadTT)") (class "Default")
      (node (ref "D34L2") (pin "TT") (pinfunction "38_TT") (pintype "bidirectional"))
    )
    (net (code "166") (name "unconnected-(D34L2-40-PadVV)") (class "Default")
      (node (ref "D34L2") (pin "VV") (pinfunction "40_VV") (pintype "bidirectional"))
    )
    (net (code "167") (name "unconnected-(D35L1-2-PadB)") (class "Default")
      (node (ref "D35L1") (pin "B") (pinfunction "2_B") (pintype "bidirectional"))
    )
    (net (code "168") (name "unconnected-(D35L1-40-PadVV)") (class "Default")
      (node (ref "D35L1") (pin "VV") (pinfunction "40_VV") (pintype "bidirectional"))
    )
    (net (code "169") (name "unconnected-(D35L2-2-PadB)") (class "Default")
      (node (ref "D35L2") (pin "B") (pinfunction "2_B") (pintype "bidirectional"))
    )
    (net (code "170") (name "unconnected-(D35L2-40-PadVV)") (class "Default")
      (node (ref "D35L2") (pin "VV") (pinfunction "40_VV") (pintype "bidirectional"))
    )
    (net (code "171") (name "unconnected-(D36L1-2-PadB)") (class "Default")
      (node (ref "D36L1") (pin "B") (pinfunction "2_B") (pintype "bidirectional"))
    )
    (net (code "172") (name "unconnected-(D36L1-40-PadVV)") (class "Default")
      (node (ref "D36L1") (pin "VV") (pinfunction "40_VV") (pintype "bidirectional"))
    )
    (net (code "173") (name "unconnected-(D36L2-2-PadB)") (class "Default")
      (node (ref "D36L2") (pin "B") (pinfunction "2_B") (pintype "bidirectional"))
    )
    (net (code "174") (name "unconnected-(D36L2-40-PadVV)") (class "Default")
      (node (ref "D36L2") (pin "VV") (pinfunction "40_VV") (pintype "bidirectional"))
    )
    (net (code "175") (name "unconnected-(E2A-Q-Pad5)") (class "Default")
      (node (ref "E2") (pin "5") (pinfunction "Q_5") (pintype "output"))
    )
    (net (code "176") (name "unconnected-(E2B-Q-Pad9)") (class "Default")
      (node (ref "E2") (pin "9") (pinfunction "Q_9") (pintype "output"))
    )
    (net (code "177") (name "unconnected-(E2B-~{Q}-Pad8)") (class "Default")
      (node (ref "E2") (pin "8") (pinfunction "~{Q}_8") (pintype "output"))
    )
    (net (code "178") (name "unconnected-(E4A-QA-Pad14)") (class "Default")
      (node (ref "E4") (pin "14") (pinfunction "QA_14") (pintype "output"))
    )
    (net (code "179") (name "unconnected-(E4A-QB-Pad13)") (class "Default")
      (node (ref "E4") (pin "13") (pinfunction "QB_13") (pintype "output"))
    )
    (net (code "180") (name "unconnected-(E4A-QC-Pad12)") (class "Default")
      (node (ref "E4") (pin "12") (pinfunction "QC_12") (pintype "output"))
    )
    (net (code "181") (name "unconnected-(E4A-QD-Pad11)") (class "Default")
      (node (ref "E4") (pin "11") (pinfunction "QD_11") (pintype "output"))
    )
    (net (code "182") (name "unconnected-(E11A-Y0-Pad15)") (class "Default")
      (node (ref "E11") (pin "15") (pinfunction "Y0_15") (pintype "output"))
    )
    (net (code "183") (name "unconnected-(E11A-Y2-Pad13)") (class "Default")
      (node (ref "E11") (pin "13") (pinfunction "Y2_13") (pintype "output"))
    )
    (net (code "184") (name "unconnected-(E11A-Y3-Pad12)") (class "Default")
      (node (ref "E11") (pin "12") (pinfunction "Y3_12") (pintype "output"))
    )
    (net (code "185") (name "unconnected-(E11A-Y4-Pad11)") (class "Default")
      (node (ref "E11") (pin "11") (pinfunction "Y4_11") (pintype "output"))
    )
    (net (code "186") (name "unconnected-(E11A-Y5-Pad10)") (class "Default")
      (node (ref "E11") (pin "10") (pinfunction "Y5_10") (pintype "output"))
    )
    (net (code "187") (name "unconnected-(E11A-Y6-Pad9)") (class "Default")
      (node (ref "E11") (pin "9") (pinfunction "Y6_9") (pintype "output"))
    )
    (net (code "188") (name "unconnected-(E12A-Y0-Pad15)") (class "Default")
      (node (ref "E12") (pin "15") (pinfunction "Y0_15") (pintype "output"))
    )
    (net (code "189") (name "unconnected-(E12A-Y1-Pad14)") (class "Default")
      (node (ref "E12") (pin "14") (pinfunction "Y1_14") (pintype "output"))
    )
    (net (code "190") (name "unconnected-(E12A-Y4-Pad11)") (class "Default")
      (node (ref "E12") (pin "11") (pinfunction "Y4_11") (pintype "output"))
    )
    (net (code "191") (name "unconnected-(E12A-Y5-Pad10)") (class "Default")
      (node (ref "E12") (pin "10") (pinfunction "Y5_10") (pintype "output"))
    )
    (net (code "192") (name "unconnected-(E12A-Y6-Pad9)") (class "Default")
      (node (ref "E12") (pin "9") (pinfunction "Y6_9") (pintype "output"))
    )
    (net (code "193") (name "unconnected-(E12A-Y7-Pad7)") (class "Default")
      (node (ref "E12") (pin "7") (pinfunction "Y7_7") (pintype "output"))
    )
    (net (code "194") (name "unconnected-(E13A-Y0-Pad15)") (class "Default")
      (node (ref "E13") (pin "15") (pinfunction "Y0_15") (pintype "output"))
    )
    (net (code "195") (name "unconnected-(E13A-Y1-Pad14)") (class "Default")
      (node (ref "E13") (pin "14") (pinfunction "Y1_14") (pintype "output"))
    )
    (net (code "196") (name "unconnected-(E13A-Y2-Pad13)") (class "Default")
      (node (ref "E13") (pin "13") (pinfunction "Y2_13") (pintype "output"))
    )
    (net (code "197") (name "unconnected-(E13A-Y3-Pad12)") (class "Default")
      (node (ref "E13") (pin "12") (pinfunction "Y3_12") (pintype "output"))
    )
    (net (code "198") (name "unconnected-(E17B-Q-Pad11)") (class "Default")
      (node (ref "E17") (pin "11") (pinfunction "Q_11") (pintype "output"))
    )
    (net (code "199") (name "unconnected-(E19A-Q-Pad15)") (class "Default")
      (node (ref "E19") (pin "15") (pinfunction "Q_15") (pintype "output"))
    )
    (net (code "200") (name "unconnected-(E19B-Q-Pad11)") (class "Default")
      (node (ref "E19") (pin "11") (pinfunction "Q_11") (pintype "output"))
    )
    (net (code "201") (name "unconnected-(E20C-O-Pad8)") (class "Default")
      (node (ref "E20") (pin "8") (pinfunction "O_8") (pintype "output"))
    )
    (net (code "202") (name "unconnected-(E21A-~{QD}-Pad11)") (class "Default")
      (node (ref "E21") (pin "11") (pinfunction "~{QD}_11") (pintype "output"))
    )
    (net (code "203") (name "unconnected-(E22A-~{QD}-Pad11)") (class "Default")
      (node (ref "E22") (pin "11") (pinfunction "~{QD}_11") (pintype "output"))
    )
    (net (code "204") (name "unconnected-(E23A-~{QD}-Pad11)") (class "Default")
      (node (ref "E23") (pin "11") (pinfunction "~{QD}_11") (pintype "output"))
    )
    (net (code "205") (name "unconnected-(E26D-O-Pad11)") (class "Default")
      (node (ref "E26") (pin "11") (pinfunction "O_11") (pintype "output"))
    )
    (net (code "206") (name "unconnected-(E30A-~{Q}-Pad6)") (class "Default")
      (node (ref "E30") (pin "6") (pinfunction "~{Q}_6") (pintype "output"))
    )
    (net (code "207") (name "unconnected-(E30B-~{Q}-Pad8)") (class "Default")
      (node (ref "E30") (pin "8") (pinfunction "~{Q}_8") (pintype "output"))
    )
    (net (code "208") (name "unconnected-(E36D-O-Pad13)") (class "Default")
      (node (ref "E36") (pin "13") (pinfunction "O_13") (pintype "output"))
    )
    (net (code "209") (name "unconnected-(LASTDEV-Pad8)") (class "Default")
      (node (ref "LASTDEV") (pin "8") (pinfunction "8_8") (pintype "passive"))
    )
    (net (code "210") (name "unconnected-(LASTDEV-Pad9)") (class "Default")
      (node (ref "LASTDEV") (pin "9") (pinfunction "9_9") (pintype "passive"))
    )
    (net (code "211") (name "unconnected-(LASTDEV-Pad10)") (class "Default")
      (node (ref "LASTDEV") (pin "10") (pinfunction "10_10") (pintype "passive"))
    )
    (net (code "212") (name "~{ACB00}") (class "Default")
      (node (ref "D34L1") (pin "D") (pinfunction "4_D") (pintype "bidirectional"))
      (node (ref "D34L2") (pin "D") (pinfunction "4_D") (pintype "bidirectional"))
      (node (ref "IC6") (pin "3") (pinfunction "O_3") (pintype "open_collector"))
    )
    (net (code "213") (name "~{ACB01}") (class "Default")
      (node (ref "D34L1") (pin "J") (pinfunction "8_J") (pintype "bidirectional"))
      (node (ref "D34L2") (pin "J") (pinfunction "8_J") (pintype "bidirectional"))
      (node (ref "IC6") (pin "5") (pinfunction "O_5") (pintype "open_collector"))
    )
    (net (code "214") (name "~{ACB02}") (class "Default")
      (node (ref "D34L1") (pin "N") (pinfunction "12_N") (pintype "bidirectional"))
      (node (ref "D34L2") (pin "N") (pinfunction "12_N") (pintype "bidirectional"))
      (node (ref "IC1") (pin "3") (pinfunction "O_3") (pintype "open_collector"))
    )
    (net (code "215") (name "~{ACB03}") (class "Default")
      (node (ref "D34L1") (pin "T") (pinfunction "16_T") (pintype "bidirectional"))
      (node (ref "D34L2") (pin "T") (pinfunction "16_T") (pintype "bidirectional"))
      (node (ref "IC2") (pin "5") (pinfunction "O_5") (pintype "open_collector"))
    )
    (net (code "216") (name "~{ACB04}") (class "Default")
      (node (ref "D34L1") (pin "X") (pinfunction "20_X") (pintype "bidirectional"))
      (node (ref "D34L2") (pin "X") (pinfunction "20_X") (pintype "bidirectional"))
      (node (ref "IC1") (pin "5") (pinfunction "O_5") (pintype "open_collector"))
    )
    (net (code "217") (name "~{ACB05}") (class "Default")
      (node (ref "D34L1") (pin "BB") (pinfunction "24_BB") (pintype "bidirectional"))
      (node (ref "D34L2") (pin "BB") (pinfunction "24_BB") (pintype "bidirectional"))
      (node (ref "IC4") (pin "3") (pinfunction "O_3") (pintype "open_collector"))
    )
    (net (code "218") (name "~{ACB06}") (class "Default")
      (node (ref "D34L1") (pin "FF") (pinfunction "28_FF") (pintype "bidirectional"))
      (node (ref "D34L2") (pin "FF") (pinfunction "28_FF") (pintype "bidirectional"))
      (node (ref "IC3") (pin "3") (pinfunction "O_3") (pintype "open_collector"))
    )
    (net (code "219") (name "~{ACB07}") (class "Default")
      (node (ref "D34L1") (pin "LL") (pinfunction "32_LL") (pintype "bidirectional"))
      (node (ref "D34L2") (pin "LL") (pinfunction "32_LL") (pintype "bidirectional"))
      (node (ref "IC3") (pin "5") (pinfunction "O_5") (pintype "open_collector"))
    )
    (net (code "220") (name "~{ACB08}") (class "Default")
      (node (ref "D34L1") (pin "RR") (pinfunction "36_RR") (pintype "bidirectional"))
      (node (ref "D34L2") (pin "RR") (pinfunction "36_RR") (pintype "bidirectional"))
      (node (ref "IC4") (pin "5") (pinfunction "O_5") (pintype "open_collector"))
    )
    (net (code "221") (name "~{ACB09}") (class "Default")
      (node (ref "D34L1") (pin "F") (pinfunction "6_F") (pintype "bidirectional"))
      (node (ref "D34L2") (pin "F") (pinfunction "6_F") (pintype "bidirectional"))
      (node (ref "IC5") (pin "3") (pinfunction "O_3") (pintype "open_collector"))
    )
    (net (code "222") (name "~{ACB10}") (class "Default")
      (node (ref "D34L1") (pin "L") (pinfunction "10_L") (pintype "bidirectional"))
      (node (ref "D34L2") (pin "L") (pinfunction "10_L") (pintype "bidirectional"))
      (node (ref "IC5") (pin "5") (pinfunction "O_5") (pintype "open_collector"))
    )
    (net (code "223") (name "~{ACB11}") (class "Default")
      (node (ref "D34L1") (pin "R") (pinfunction "14_R") (pintype "bidirectional"))
      (node (ref "D34L2") (pin "R") (pinfunction "14_R") (pintype "bidirectional"))
      (node (ref "IC2") (pin "3") (pinfunction "O_3") (pintype "open_collector"))
    )
    (net (code "224") (name "~{ACCLEAR}") (class "Default")
      (node (ref "D34L1") (pin "DD") (pinfunction "26_DD") (pintype "bidirectional"))
      (node (ref "D34L2") (pin "DD") (pinfunction "26_DD") (pintype "bidirectional"))
      (node (ref "IC7") (pin "3") (pinfunction "O_3") (pintype "open_collector"))
    )
    (net (code "225") (name "~{BMB03}") (class "Default")
      (node (ref "D35L1") (pin "T") (pinfunction "16_T") (pintype "bidirectional"))
      (node (ref "D35L2") (pin "T") (pinfunction "16_T") (pintype "bidirectional"))
    )
    (net (code "226") (name "~{BMB04}") (class "Default")
      (node (ref "D35L1") (pin "BB") (pinfunction "24_BB") (pintype "bidirectional"))
      (node (ref "D35L2") (pin "BB") (pinfunction "24_BB") (pintype "bidirectional"))
    )
    (net (code "227") (name "~{BMB05}") (class "Default")
      (node (ref "D35L1") (pin "LL") (pinfunction "32_LL") (pintype "bidirectional"))
      (node (ref "D35L2") (pin "LL") (pinfunction "32_LL") (pintype "bidirectional"))
    )
    (net (code "228") (name "~{BMB06}") (class "Default")
      (node (ref "D35L1") (pin "F") (pinfunction "6_F") (pintype "bidirectional"))
      (node (ref "D35L2") (pin "F") (pinfunction "6_F") (pintype "bidirectional"))
    )
    (net (code "229") (name "~{BMB07}") (class "Default")
      (node (ref "D35L1") (pin "R") (pinfunction "14_R") (pintype "bidirectional"))
      (node (ref "D35L2") (pin "R") (pinfunction "14_R") (pintype "bidirectional"))
    )
    (net (code "230") (name "~{BMB08}") (class "Default")
      (node (ref "D35L1") (pin "Z") (pinfunction "22_Z") (pintype "bidirectional"))
      (node (ref "D35L2") (pin "Z") (pinfunction "22_Z") (pintype "bidirectional"))
    )
    (net (code "231") (name "~{BRUN}") (class "Default")
      (node (ref "D34L1") (pin "JJ") (pinfunction "30_JJ") (pintype "bidirectional"))
      (node (ref "D34L2") (pin "JJ") (pinfunction "30_JJ") (pintype "bidirectional"))
    )
    (net (code "232") (name "~{CLK_PARITY}") (class "Default")
      (node (ref "E17") (pin "6") (pinfunction "CLK_6") (pintype "input"))
      (node (ref "E32") (pin "6") (pinfunction "O_6") (pintype "output"))
      (node (ref "E5") (pin "4") (pinfunction "I0_4") (pintype "input"))
      (node (ref "E5") (pin "5") (pinfunction "I1_5") (pintype "input"))
    )
    (net (code "233") (name "~{DONE}") (class "Default")
      (node (ref "E10") (pin "4") (pinfunction "I1_4") (pintype "input"))
      (node (ref "E25") (pin "4") (pinfunction "O_4") (pintype "output"))
      (node (ref "E31") (pin "12") (pinfunction "I2_12") (pintype "input"))
    )
    (net (code "234") (name "~{ENB_BUF_LD}") (class "Default")
      (node (ref "E21") (pin "9") (pinfunction "S/~{L}_9") (pintype "input"))
      (node (ref "E22") (pin "9") (pinfunction "S/~{L}_9") (pintype "input"))
      (node (ref "E23") (pin "9") (pinfunction "S/~{L}_9") (pintype "input"))
      (node (ref "E24") (pin "11") (pinfunction "O_11") (pintype "output"))
      (node (ref "E32") (pin "13") (pinfunction "I2_13") (pintype "input"))
      (node (ref "E32") (pin "2") (pinfunction "I1_2") (pintype "input"))
      (node (ref "E4") (pin "9") (pinfunction "LD_9") (pintype "input"))
    )
    (net (code "235") (name "~{INIT1}") (class "Default")
      (node (ref "E11") (pin "7") (pinfunction "Y7_7") (pintype "output"))
      (node (ref "E2") (pin "4") (pinfunction "PRE_4") (pintype "input"))
    )
    (net (code "236") (name "~{INIT4}") (class "Default")
      (node (ref "E13") (pin "7") (pinfunction "Y7_7") (pintype "output"))
      (node (ref "E2") (pin "3") (pinfunction "CLK_3") (pintype "input"))
    )
    (net (code "237") (name "~{INIT}") (class "Default")
      (node (ref "E15") (pin "6") (pinfunction "O_6") (pintype "output"))
      (node (ref "E16") (pin "1") (pinfunction "CLR_1") (pintype "input"))
      (node (ref "E16") (pin "13") (pinfunction "CLR_13") (pintype "input"))
      (node (ref "E17") (pin "3") (pinfunction "CLR_3") (pintype "input"))
      (node (ref "E19") (pin "3") (pinfunction "CLR_3") (pintype "input"))
      (node (ref "E19") (pin "8") (pinfunction "CLR_8") (pintype "input"))
      (node (ref "E21") (pin "1") (pinfunction "CLR_1") (pintype "input"))
      (node (ref "E22") (pin "1") (pinfunction "CLR_1") (pintype "input"))
      (node (ref "E23") (pin "1") (pinfunction "CLR_1") (pintype "input"))
      (node (ref "E24") (pin "9") (pinfunction "I0_9") (pintype "input"))
      (node (ref "E30") (pin "1") (pinfunction "CLR_1") (pintype "input"))
      (node (ref "E4") (pin "1") (pinfunction "CLR_1") (pintype "input"))
    )
    (net (code "238") (name "~{INTR4}") (class "Default")
      (node (ref "E13") (pin "9") (pinfunction "Y6_9") (pintype "output"))
      (node (ref "E30") (pin "3") (pinfunction "CLK_3") (pintype "input"))
    )
    (net (code "239") (name "~{INT_RQ}") (class "Default")
      (node (ref "D34L1") (pin "Z") (pinfunction "22_Z") (pintype "bidirectional"))
      (node (ref "D34L2") (pin "Z") (pinfunction "22_Z") (pintype "bidirectional"))
      (node (ref "IC10") (pin "5") (pinfunction "O_5") (pintype "open_collector"))
    )
    (net (code "240") (name "~{IOS}") (class "Default")
      (node (ref "D34L1") (pin "V") (pinfunction "18_V") (pintype "bidirectional"))
      (node (ref "D34L2") (pin "V") (pinfunction "18_V") (pintype "bidirectional"))
      (node (ref "IC10") (pin "3") (pinfunction "O_3") (pintype "open_collector"))
    )
    (net (code "241") (name "~{LCD1}") (class "Default")
      (node (ref "E10") (pin "9") (pinfunction "I0_9") (pintype "input"))
      (node (ref "E11") (pin "14") (pinfunction "Y1_14") (pintype "output"))
      (node (ref "E16") (pin "11") (pinfunction "CLK_11") (pintype "input"))
      (node (ref "E16") (pin "3") (pinfunction "CLK_3") (pintype "input"))
      (node (ref "E24") (pin "5") (pinfunction "I1_5") (pintype "input"))
      (node (ref "E25") (pin "5") (pinfunction "I_5") (pintype "input"))
    )
    (net (code "242") (name "~{MAINT}") (class "Default")
      (node (ref "E10") (pin "3") (pinfunction "I0_3") (pintype "input"))
      (node (ref "E16") (pin "8") (pinfunction "~{Q}_8") (pintype "output"))
      (node (ref "E17") (pin "2") (pinfunction "PRE_2") (pintype "input"))
      (node (ref "E19") (pin "2") (pinfunction "PRE_2") (pintype "input"))
      (node (ref "E19") (pin "7") (pinfunction "PRE_7") (pintype "input"))
      (node (ref "E24") (pin "13") (pinfunction "I1_13") (pintype "input"))
      (node (ref "E31") (pin "10") (pinfunction "I1_10") (pintype "input"))
      (node (ref "E31") (pin "5") (pinfunction "I3_5") (pintype "input"))
      (node (ref "E31") (pin "9") (pinfunction "I0_9") (pintype "input"))
    )
    (net (code "243") (name "~{MYDEV}") (class "Default")
      (node (ref "E11") (pin "4") (pinfunction "G2A_4") (pintype "input"))
      (node (ref "E12") (pin "4") (pinfunction "G2A_4") (pintype "input"))
      (node (ref "E13") (pin "4") (pinfunction "G2A_4") (pintype "input"))
      (node (ref "IOT") (pin "1") (pinfunction "P_1") (pintype "passive"))
    )
    (net (code "244") (name "~{PARITY}") (class "Default")
      (node (ref "E15") (pin "12") (pinfunction "I0_12") (pintype "input"))
      (node (ref "E17") (pin "10") (pinfunction "~{Q}_10") (pintype "output"))
    )
    (net (code "245") (name "~{RX_12_BIT}") (class "Default")
      (node (ref "DRIVE") (pin "FF") (pinfunction "28_FF") (pintype "bidirectional"))
      (node (ref "IC8") (pin "3") (pinfunction "O_3") (pintype "open_collector"))
      (node (ref "R16") (pin "2") (pinfunction "2_2") (pintype "passive"))
      (node (ref "R7") (pin "1") (pinfunction "1_1") (pintype "passive"))
    )
    (net (code "246") (name "~{RX_DATA}") (class "Default")
      (node (ref "DRIVE") (pin "BB") (pinfunction "24_BB") (pintype "bidirectional"))
      (node (ref "E35") (pin "2") (pinfunction "I0_2") (pintype "input"))
      (node (ref "IC7") (pin "5") (pinfunction "O_5") (pintype "open_collector"))
      (node (ref "R17") (pin "2") (pinfunction "2_2") (pintype "passive"))
      (node (ref "R8") (pin "1") (pinfunction "1_1") (pintype "passive"))
    )
    (net (code "247") (name "~{RX_DONE}") (class "Default")
      (node (ref "DRIVE") (pin "X") (pinfunction "20_X") (pintype "bidirectional"))
      (node (ref "E36") (pin "8") (pinfunction "I0_8") (pintype "input"))
      (node (ref "R13") (pin "2") (pinfunction "2_2") (pintype "passive"))
      (node (ref "R4") (pin "1") (pinfunction "1_1") (pintype "passive"))
    )
    (net (code "248") (name "~{RX_ERROR}") (class "Default")
      (node (ref "DRIVE") (pin "J") (pinfunction "8_J") (pintype "bidirectional"))
      (node (ref "E36") (pin "3") (pinfunction "I1_3") (pintype "input"))
      (node (ref "R14") (pin "2") (pinfunction "2_2") (pintype "passive"))
      (node (ref "R5") (pin "1") (pinfunction "1_1") (pintype "passive"))
    )
    (net (code "249") (name "~{RX_INIT}") (class "Default")
      (node (ref "DRIVE") (pin "N") (pinfunction "12_N") (pintype "bidirectional"))
      (node (ref "IC8") (pin "5") (pinfunction "O_5") (pintype "open_collector"))
      (node (ref "R20") (pin "1") (pinfunction "1_1") (pintype "passive"))
      (node (ref "R9") (pin "1") (pinfunction "1_1") (pintype "passive"))
    )
    (net (code "250") (name "~{RX_OUT}") (class "Default")
      (node (ref "DRIVE") (pin "RR") (pinfunction "36_RR") (pintype "bidirectional"))
      (node (ref "E35") (pin "8") (pinfunction "I0_8") (pintype "input"))
      (node (ref "R12") (pin "2") (pinfunction "2_2") (pintype "passive"))
      (node (ref "R3") (pin "1") (pinfunction "1_1") (pintype "passive"))
    )
    (net (code "251") (name "~{RX_RUN}") (class "Default")
      (node (ref "DRIVE") (pin "D") (pinfunction "4_D") (pintype "bidirectional"))
      (node (ref "IC9") (pin "5") (pinfunction "O_5") (pintype "open_collector"))
      (node (ref "R15") (pin "2") (pinfunction "2_2") (pintype "passive"))
      (node (ref "R6") (pin "1") (pinfunction "1_1") (pintype "passive"))
    )
    (net (code "252") (name "~{RX_SHIFT}") (class "Default")
      (node (ref "DRIVE") (pin "LL") (pinfunction "32_LL") (pintype "bidirectional"))
      (node (ref "E35") (pin "5") (pinfunction "I0_5") (pintype "input"))
      (node (ref "R10") (pin "2") (pinfunction "2_2") (pintype "passive"))
      (node (ref "R2") (pin "1") (pinfunction "1_1") (pintype "passive"))
    )
    (net (code "253") (name "~{RX_TR_REQ}") (class "Default")
      (node (ref "DRIVE") (pin "T") (pinfunction "16_T") (pintype "bidirectional"))
      (node (ref "E36") (pin "5") (pinfunction "I0_5") (pintype "input"))
      (node (ref "R1") (pin "1") (pinfunction "1_1") (pintype "passive"))
      (node (ref "R11") (pin "2") (pinfunction "2_2") (pintype "passive"))
    )
    (net (code "254") (name "~{SDN4}") (class "Default")
      (node (ref "E13") (pin "10") (pinfunction "Y5_10") (pintype "output"))
      (node (ref "E18") (pin "8") (pinfunction "I0_8") (pintype "input"))
    )
    (net (code "255") (name "~{SER4}") (class "Default")
      (node (ref "E13") (pin "11") (pinfunction "Y4_11") (pintype "output"))
      (node (ref "E18") (pin "5") (pinfunction "I0_5") (pintype "input"))
    )
    (net (code "256") (name "~{STR2}") (class "Default")
      (node (ref "E12") (pin "12") (pinfunction "Y3_12") (pintype "output"))
      (node (ref "E18") (pin "2") (pinfunction "I0_2") (pintype "input"))
    )
    (net (code "257") (name "~{XDR2}") (class "Default")
      (node (ref "E12") (pin "13") (pinfunction "Y2_13") (pintype "output"))
      (node (ref "E24") (pin "4") (pinfunction "I0_4") (pintype "input"))
      (node (ref "E25") (pin "9") (pinfunction "I_9") (pintype "input"))
      (node (ref "E35") (pin "12") (pinfunction "I1_12") (pintype "input"))
      (node (ref "E5") (pin "10") (pinfunction "I1_10") (pintype "input"))
      (node (ref "E5") (pin "9") (pinfunction "I0_9") (pintype "input"))
    )
  )
)
